# MultiSpikeHoldSchem.net
KiCad netlist of a schematic drawn in Altium Designer
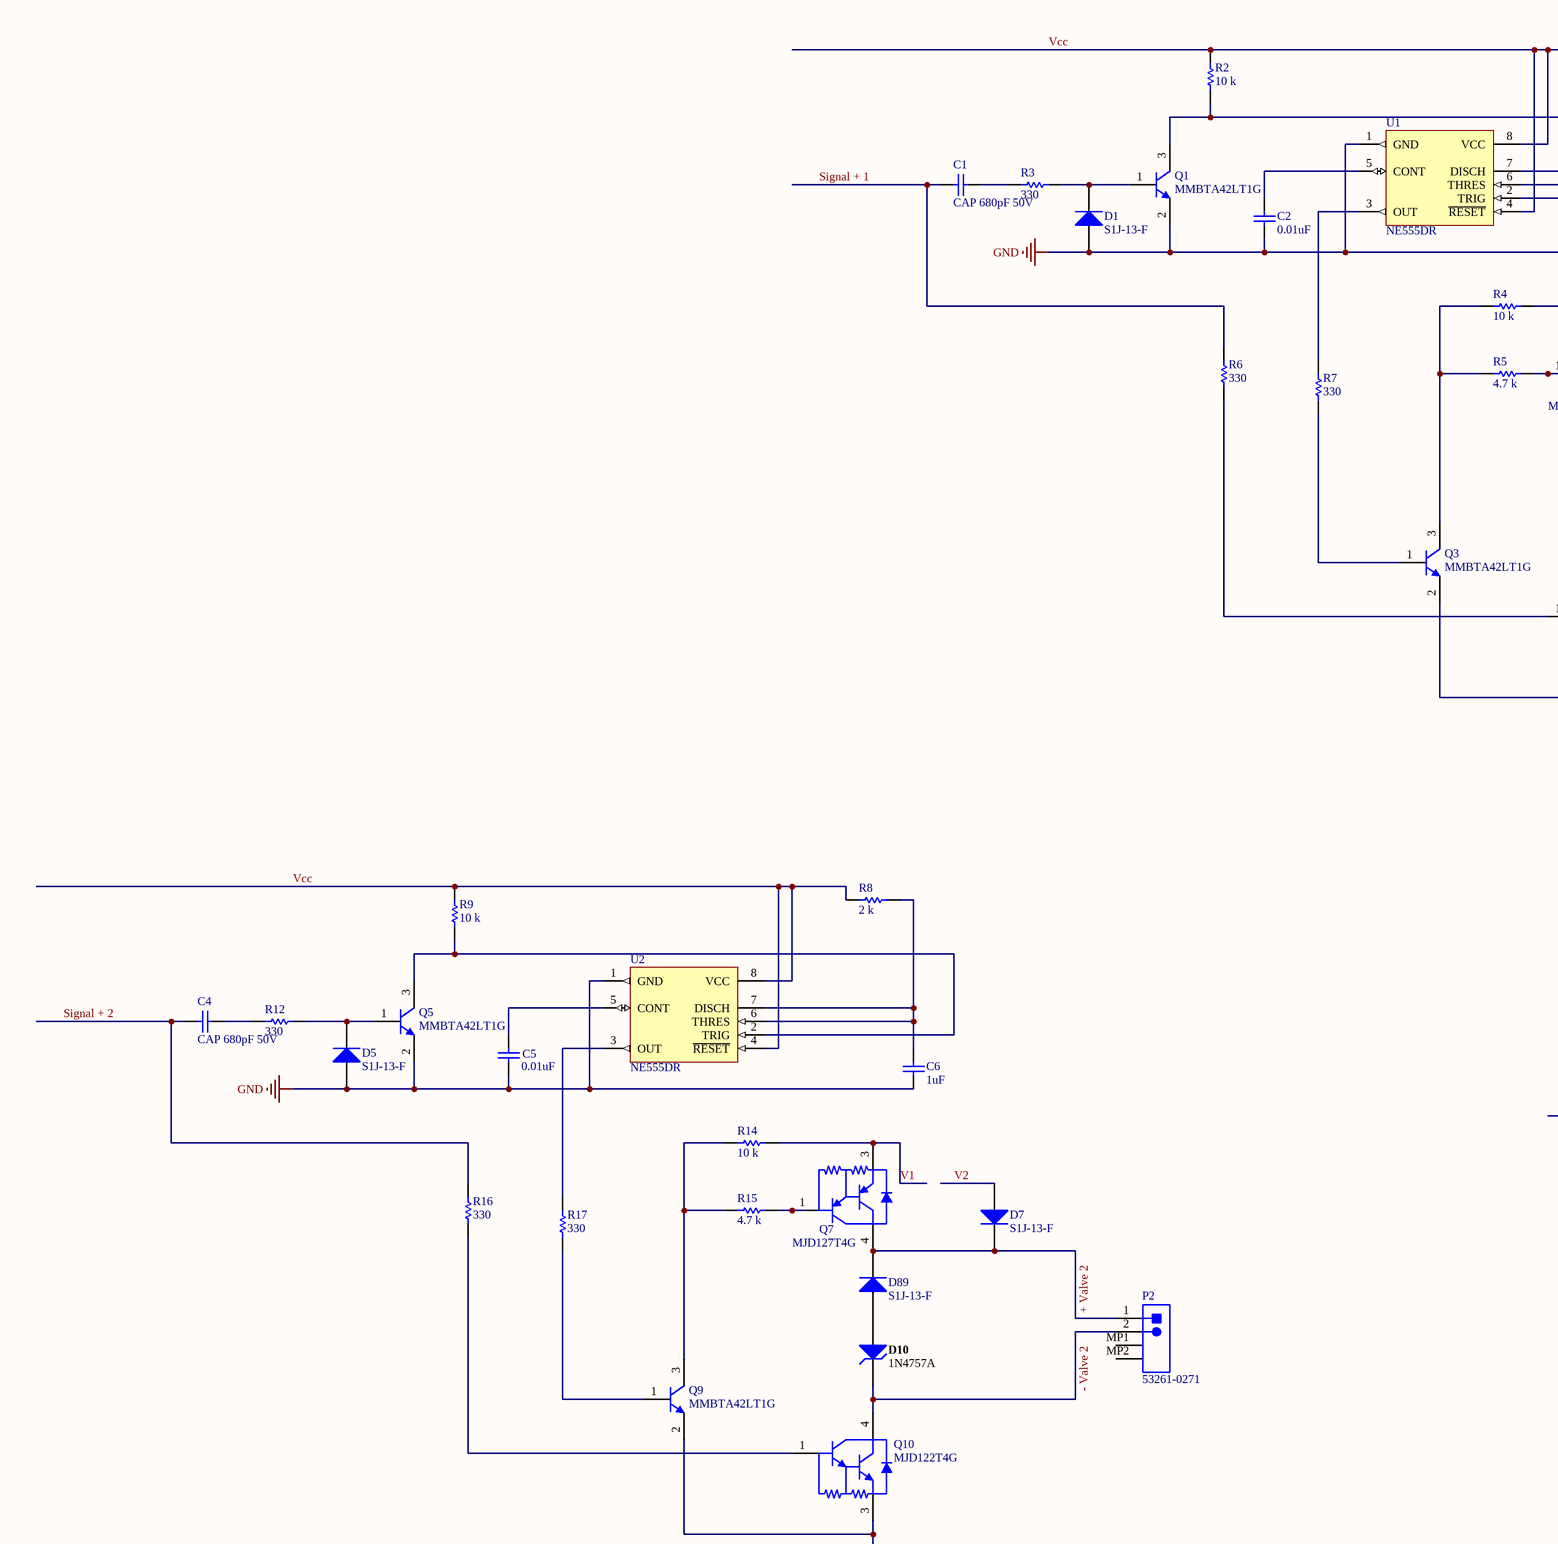
[diagram p0: MultiSpikeHoldSchem.SchDoc, top left]
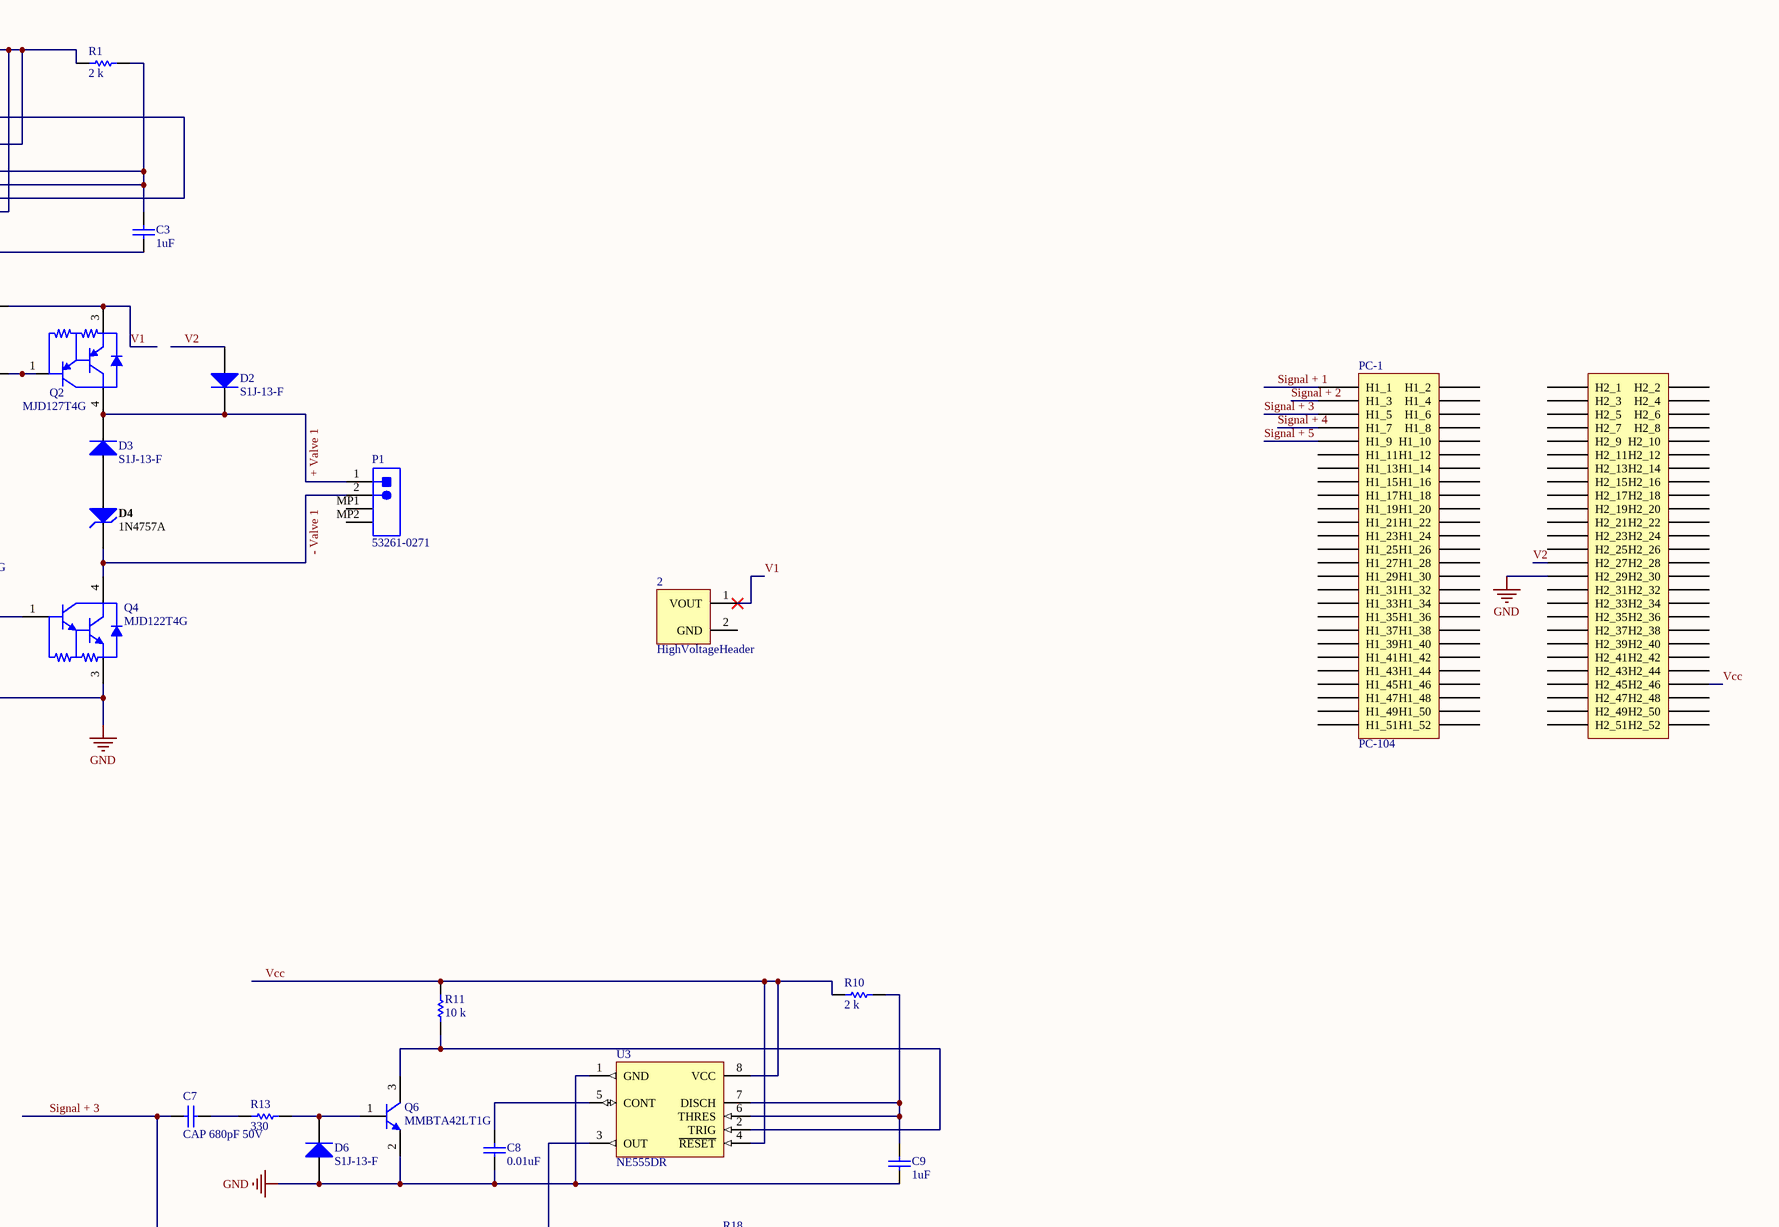
[diagram p1: MultiSpikeHoldSchem.SchDoc, top right]
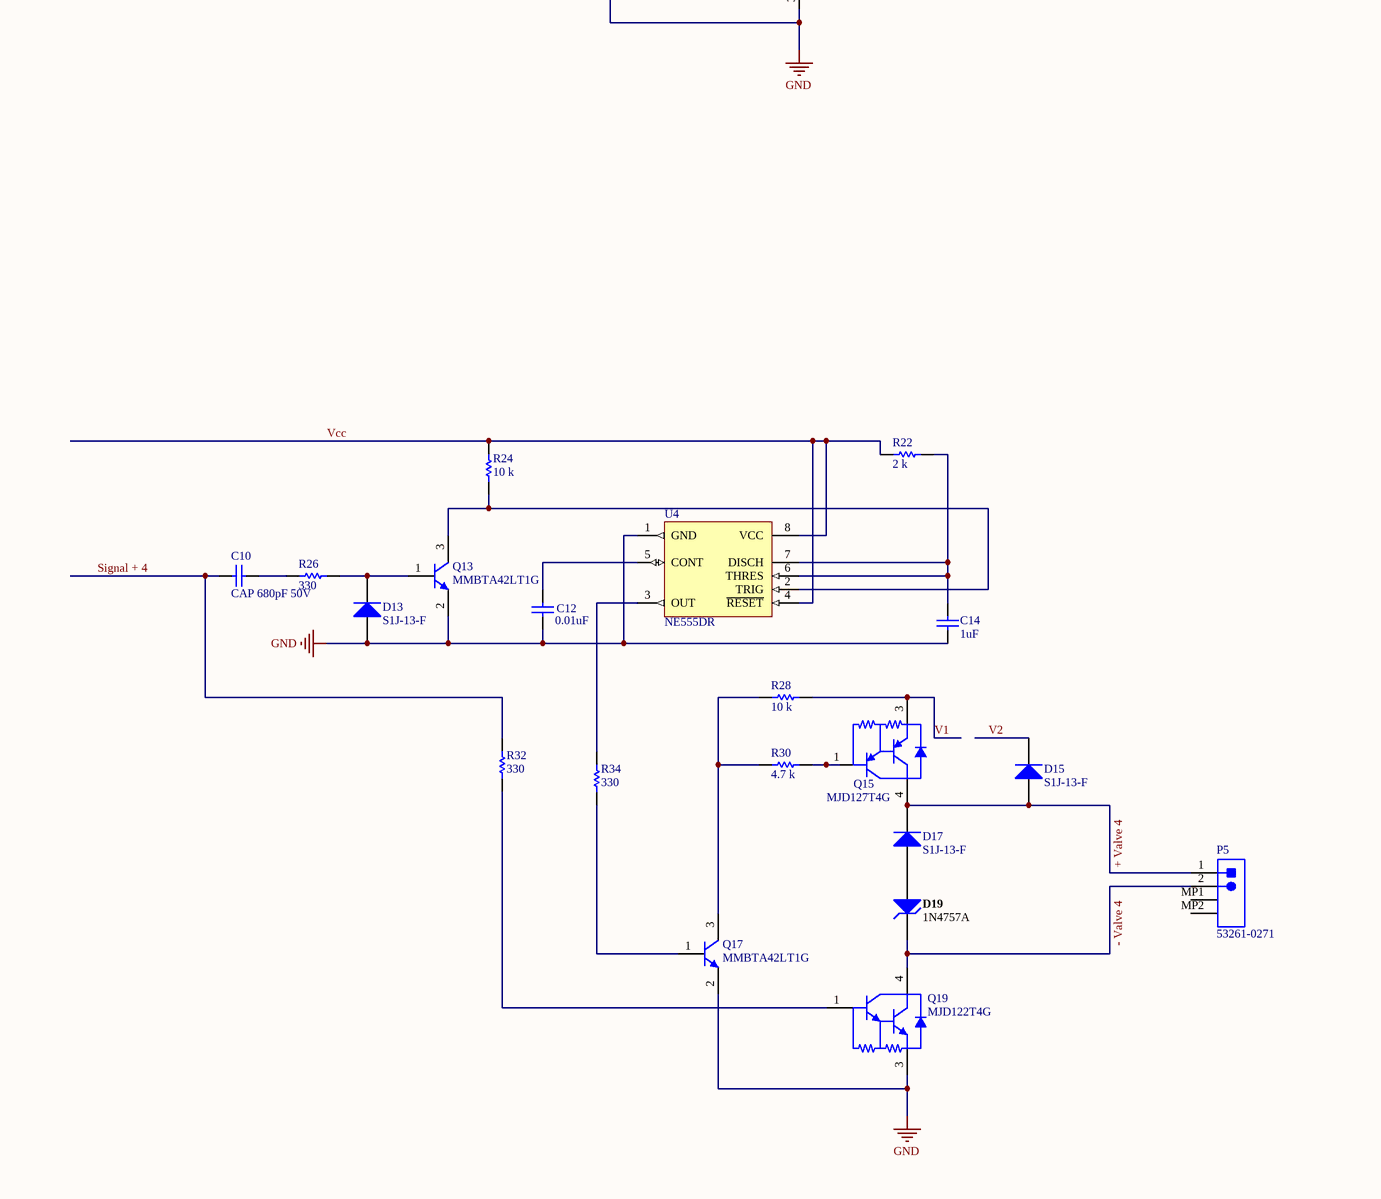
[diagram p2: MultiSpikeHoldSchem.SchDoc, bottom left]
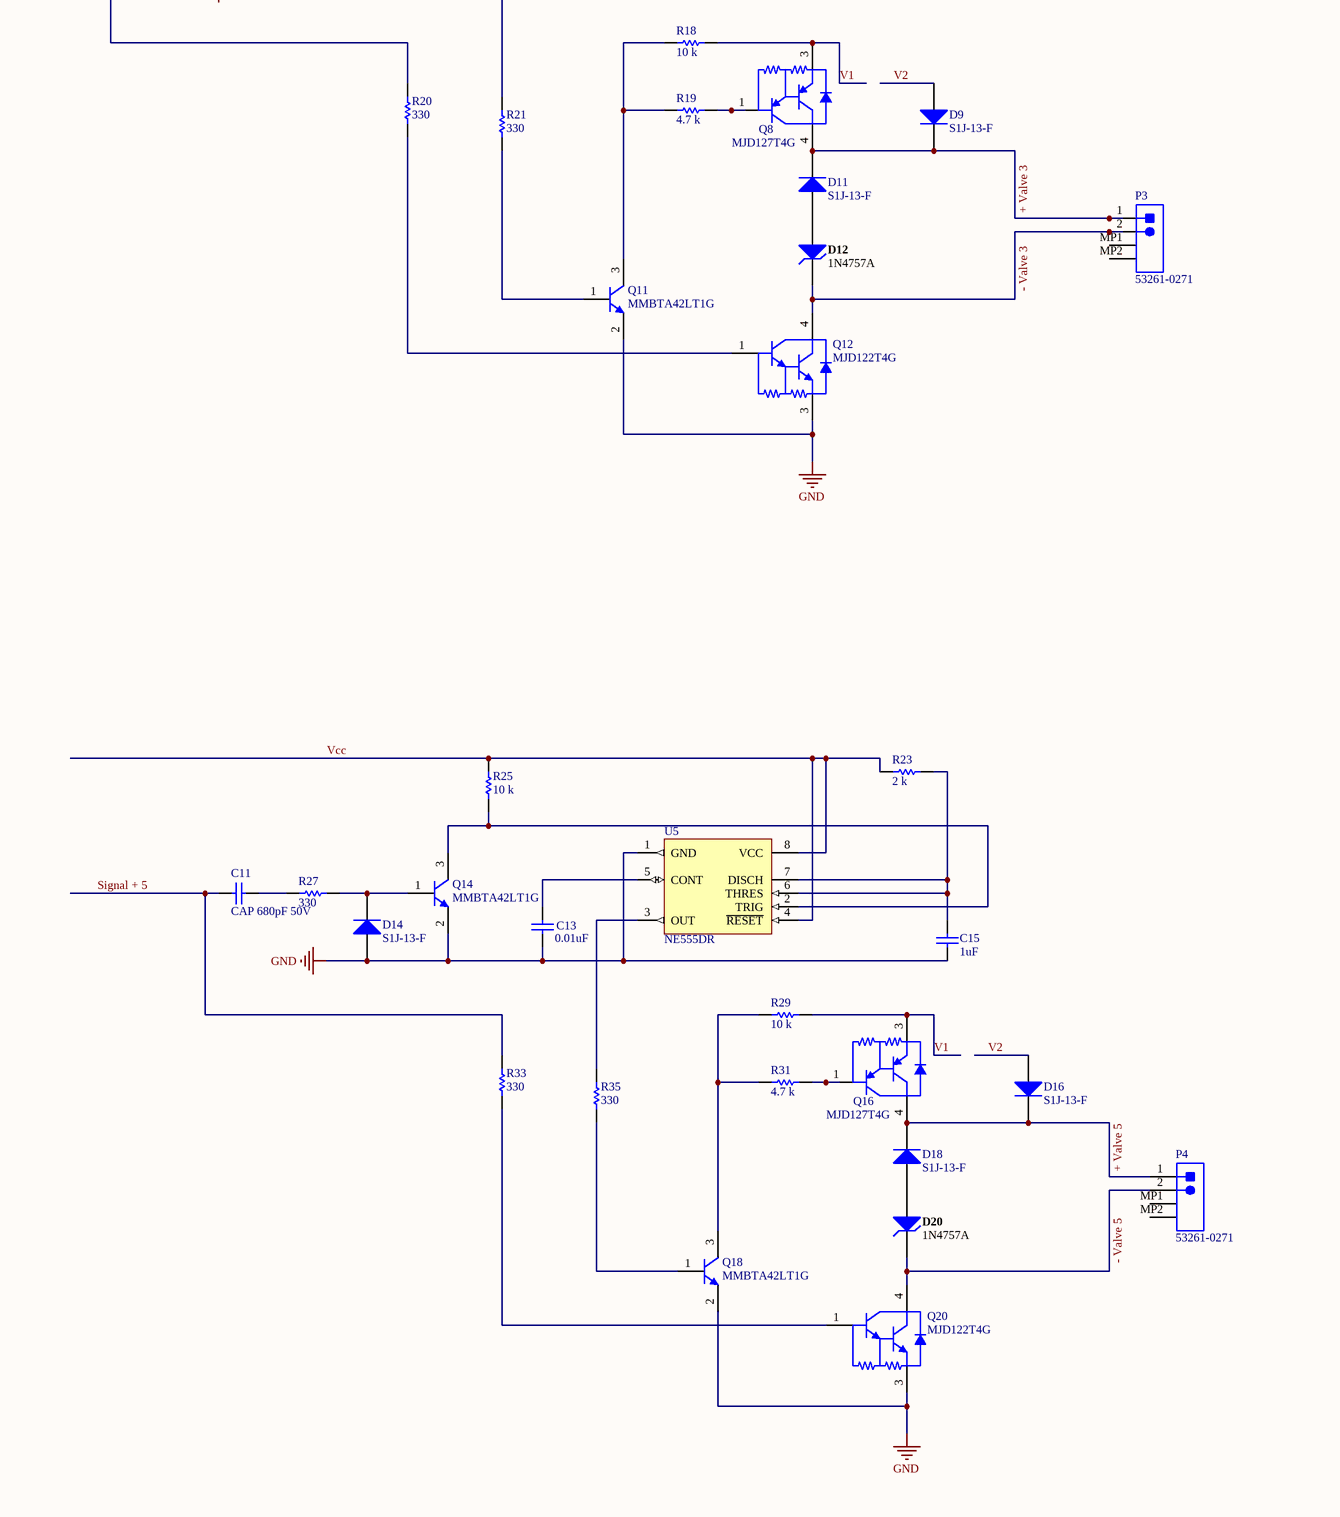
[diagram p3: MultiSpikeHoldSchem.SchDoc, bottom right]

(export (version "E")
  (design (tool "Eeschema 10.0.6"))
  (components
    (comp (ref "2")
      (value "HighVoltageHeader")
      (footprint "Header")
      (libsource (lib "AdapterBoard") (part "HighVoltageHeader"))
    )
    (comp (ref "C1")
      (value "CAP 680pF 50V")
      (footprint "CAPC1005X55X25ML05T10")
      (description "Chip Capacitor, 680 pF, +/- 10%, 50 V, -55 to 125 degC, 0402 (1005 Metric), RoHS, Tape and Reel")
      (fields (field (name "TOLERANCE") "10%") (field (name "MANUFACTURER") "Basic Passives"))
      (libsource (lib "Altium Content Vault") (part "CAP-NP-2"))
    )
    (comp (ref "C2")
      (value "0.01uF")
      (footprint "CAPC2013X70X45ML10T25")
      (description "Chip Capacitor, 10 nF, +/- 10%, 50 V, -55 to 125 degC, 0805 (2012 Metric), RoHS, Tape and Reel")
      (fields (field (name "TOLERANCE") "10%") (field (name "MANUFACTURER") "Murata"))
      (libsource (lib "Altium Content Vault") (part "CAP-NP-2"))
    )
    (comp (ref "C3")
      (value "1uF")
      (footprint "CAPC1206(3216)110_L")
      (description "CAP 1uF 50V ±10% 1206 (3216 Metric) Thickness 1.1mm SMD")
      (fields (field (name "TOLERANCE") "Â±10%"))
      (libsource (lib "Altium Content Vault") (part "CAP"))
    )
    (comp (ref "C4")
      (value "CAP 680pF 50V")
      (footprint "CAPC1005X55X25ML05T10")
      (description "Chip Capacitor, 680 pF, +/- 10%, 50 V, -55 to 125 degC, 0402 (1005 Metric), RoHS, Tape and Reel")
      (fields (field (name "TOLERANCE") "10%") (field (name "MANUFACTURER") "Basic Passives"))
      (libsource (lib "Altium Content Vault") (part "CAP-NP-2"))
    )
    (comp (ref "C5")
      (value "0.01uF")
      (footprint "CAPC2013X70X45ML10T25")
      (description "Chip Capacitor, 10 nF, +/- 10%, 50 V, -55 to 125 degC, 0805 (2012 Metric), RoHS, Tape and Reel")
      (fields (field (name "TOLERANCE") "10%") (field (name "MANUFACTURER") "Murata"))
      (libsource (lib "Altium Content Vault") (part "CAP-NP-2"))
    )
    (comp (ref "C6")
      (value "1uF")
      (footprint "CAPC1206(3216)110_L")
      (description "CAP 1uF 50V ±10% 1206 (3216 Metric) Thickness 1.1mm SMD")
      (fields (field (name "TOLERANCE") "Â±10%"))
      (libsource (lib "Altium Content Vault") (part "CAP"))
    )
    (comp (ref "C7")
      (value "CAP 680pF 50V")
      (footprint "CAPC1005X55X25ML05T10")
      (description "Chip Capacitor, 680 pF, +/- 10%, 50 V, -55 to 125 degC, 0402 (1005 Metric), RoHS, Tape and Reel")
      (fields (field (name "TOLERANCE") "10%") (field (name "MANUFACTURER") "Basic Passives"))
      (libsource (lib "Altium Content Vault") (part "CAP-NP-2"))
    )
    (comp (ref "C8")
      (value "0.01uF")
      (footprint "CAPC2013X70X45ML10T25")
      (description "Chip Capacitor, 10 nF, +/- 10%, 50 V, -55 to 125 degC, 0805 (2012 Metric), RoHS, Tape and Reel")
      (fields (field (name "TOLERANCE") "10%") (field (name "MANUFACTURER") "Murata"))
      (libsource (lib "Altium Content Vault") (part "CAP-NP-2"))
    )
    (comp (ref "C9")
      (value "1uF")
      (footprint "CAPC1206(3216)110_L")
      (description "CAP 1uF 50V ±10% 1206 (3216 Metric) Thickness 1.1mm SMD")
      (fields (field (name "TOLERANCE") "Â±10%"))
      (libsource (lib "Altium Content Vault") (part "CAP"))
    )
    (comp (ref "C10")
      (value "CAP 680pF 50V")
      (footprint "CAPC1005X55X25ML05T10")
      (description "Chip Capacitor, 680 pF, +/- 10%, 50 V, -55 to 125 degC, 0402 (1005 Metric), RoHS, Tape and Reel")
      (fields (field (name "TOLERANCE") "10%") (field (name "MANUFACTURER") "Basic Passives"))
      (libsource (lib "Altium Content Vault") (part "CAP-NP-2"))
    )
    (comp (ref "C11")
      (value "CAP 680pF 50V")
      (footprint "CAPC1005X55X25ML05T10")
      (description "Chip Capacitor, 680 pF, +/- 10%, 50 V, -55 to 125 degC, 0402 (1005 Metric), RoHS, Tape and Reel")
      (fields (field (name "TOLERANCE") "10%") (field (name "MANUFACTURER") "Basic Passives"))
      (libsource (lib "Altium Content Vault") (part "CAP-NP-2"))
    )
    (comp (ref "C12")
      (value "0.01uF")
      (footprint "CAPC2013X70X45ML10T25")
      (description "Chip Capacitor, 10 nF, +/- 10%, 50 V, -55 to 125 degC, 0805 (2012 Metric), RoHS, Tape and Reel")
      (fields (field (name "TOLERANCE") "10%") (field (name "MANUFACTURER") "Murata"))
      (libsource (lib "Altium Content Vault") (part "CAP-NP-2"))
    )
    (comp (ref "C13")
      (value "0.01uF")
      (footprint "CAPC2013X70X45ML10T25")
      (description "Chip Capacitor, 10 nF, +/- 10%, 50 V, -55 to 125 degC, 0805 (2012 Metric), RoHS, Tape and Reel")
      (fields (field (name "TOLERANCE") "10%") (field (name "MANUFACTURER") "Murata"))
      (libsource (lib "Altium Content Vault") (part "CAP-NP-2"))
    )
    (comp (ref "C14")
      (value "1uF")
      (footprint "CAPC1206(3216)110_L")
      (description "CAP 1uF 50V ±10% 1206 (3216 Metric) Thickness 1.1mm SMD")
      (fields (field (name "TOLERANCE") "Â±10%"))
      (libsource (lib "Altium Content Vault") (part "CAP"))
    )
    (comp (ref "C15")
      (value "1uF")
      (footprint "CAPC1206(3216)110_L")
      (description "CAP 1uF 50V ±10% 1206 (3216 Metric) Thickness 1.1mm SMD")
      (fields (field (name "TOLERANCE") "Â±10%"))
      (libsource (lib "Altium Content Vault") (part "CAP"))
    )
    (comp (ref "D1")
      (value "S1J-13-F")
      (footprint "DIOD-S1M-13-F-SMA-2_V")
      (fields (field (name "MANUFACTURER") "Diodes Inc") (field (name "PARTNUMBER") "S1M-13-F"))
      (libsource (lib "Altium Content Vault") (part "DIOD-D-A1K2-2"))
    )
    (comp (ref "D2")
      (value "S1J-13-F")
      (footprint "DIOD-S1M-13-F-SMA-2_V")
      (fields (field (name "MANUFACTURER") "Diodes Inc") (field (name "PARTNUMBER") "S1M-13-F"))
      (libsource (lib "Altium Content Vault") (part "DIOD-D-A1K2-2"))
    )
    (comp (ref "D3")
      (value "S1J-13-F")
      (footprint "DIOD-S1M-13-F-SMA-2_V")
      (fields (field (name "MANUFACTURER") "Diodes Inc") (field (name "PARTNUMBER") "S1M-13-F"))
      (libsource (lib "Altium Content Vault") (part "DIOD-D-A1K2-2"))
    )
    (comp (ref "D4")
      (value "1N4757A")
      (footprint "FAIR-DO-41-2_V")
      (description "Zener Diode, 51V, 1W, 5%, -65 to 200 degC, 2-Pin DO-41, Body 2.72 x 5.2 mm, RoHS")
      (fields (field (name "MANUFACTURER") "Fairchild Semiconductor") (field (name "TOLERANCE") "5%"))
      (libsource (lib "Altium Content Vault") (part "FAIR-DZEN-A1K2-2"))
    )
    (comp (ref "D5")
      (value "S1J-13-F")
      (footprint "DIOD-S1M-13-F-SMA-2_V")
      (fields (field (name "MANUFACTURER") "Diodes Inc") (field (name "PARTNUMBER") "S1M-13-F"))
      (libsource (lib "Altium Content Vault") (part "DIOD-D-A1K2-2"))
    )
    (comp (ref "D6")
      (value "S1J-13-F")
      (footprint "DIOD-S1M-13-F-SMA-2_V")
      (fields (field (name "MANUFACTURER") "Diodes Inc") (field (name "PARTNUMBER") "S1M-13-F"))
      (libsource (lib "Altium Content Vault") (part "DIOD-D-A1K2-2"))
    )
    (comp (ref "D7")
      (value "S1J-13-F")
      (footprint "DIOD-S1M-13-F-SMA-2_V")
      (fields (field (name "MANUFACTURER") "Diodes Inc") (field (name "PARTNUMBER") "S1M-13-F"))
      (libsource (lib "Altium Content Vault") (part "DIOD-D-A1K2-2"))
    )
    (comp (ref "D9")
      (value "S1J-13-F")
      (footprint "DIOD-S1M-13-F-SMA-2_V")
      (fields (field (name "MANUFACTURER") "Diodes Inc") (field (name "PARTNUMBER") "S1M-13-F"))
      (libsource (lib "Altium Content Vault") (part "DIOD-D-A1K2-2"))
    )
    (comp (ref "D10")
      (value "1N4757A")
      (footprint "FAIR-DO-41-2_V")
      (description "Zener Diode, 51V, 1W, 5%, -65 to 200 degC, 2-Pin DO-41, Body 2.72 x 5.2 mm, RoHS")
      (fields (field (name "MANUFACTURER") "Fairchild Semiconductor") (field (name "TOLERANCE") "5%"))
      (libsource (lib "Altium Content Vault") (part "FAIR-DZEN-A1K2-2"))
    )
    (comp (ref "D11")
      (value "S1J-13-F")
      (footprint "DIOD-S1M-13-F-SMA-2_V")
      (fields (field (name "MANUFACTURER") "Diodes Inc") (field (name "PARTNUMBER") "S1M-13-F"))
      (libsource (lib "Altium Content Vault") (part "DIOD-D-A1K2-2"))
    )
    (comp (ref "D12")
      (value "1N4757A")
      (footprint "FAIR-DO-41-2_V")
      (description "Zener Diode, 51V, 1W, 5%, -65 to 200 degC, 2-Pin DO-41, Body 2.72 x 5.2 mm, RoHS")
      (fields (field (name "MANUFACTURER") "Fairchild Semiconductor") (field (name "TOLERANCE") "5%"))
      (libsource (lib "Altium Content Vault") (part "FAIR-DZEN-A1K2-2"))
    )
    (comp (ref "D13")
      (value "S1J-13-F")
      (footprint "DIOD-S1M-13-F-SMA-2_V")
      (fields (field (name "MANUFACTURER") "Diodes Inc") (field (name "PARTNUMBER") "S1M-13-F"))
      (libsource (lib "Altium Content Vault") (part "DIOD-D-A1K2-2"))
    )
    (comp (ref "D14")
      (value "S1J-13-F")
      (footprint "DIOD-S1M-13-F-SMA-2_V")
      (fields (field (name "MANUFACTURER") "Diodes Inc") (field (name "PARTNUMBER") "S1M-13-F"))
      (libsource (lib "Altium Content Vault") (part "DIOD-D-A1K2-2"))
    )
    (comp (ref "D15")
      (value "S1J-13-F")
      (footprint "DIOD-S1M-13-F-SMA-2_V")
      (fields (field (name "MANUFACTURER") "Diodes Inc") (field (name "PARTNUMBER") "S1M-13-F"))
      (libsource (lib "Altium Content Vault") (part "DIOD-D-A1K2-2"))
    )
    (comp (ref "D16")
      (value "S1J-13-F")
      (footprint "DIOD-S1M-13-F-SMA-2_V")
      (fields (field (name "MANUFACTURER") "Diodes Inc") (field (name "PARTNUMBER") "S1M-13-F"))
      (libsource (lib "Altium Content Vault") (part "DIOD-D-A1K2-2"))
    )
    (comp (ref "D17")
      (value "S1J-13-F")
      (footprint "DIOD-S1M-13-F-SMA-2_V")
      (fields (field (name "MANUFACTURER") "Diodes Inc") (field (name "PARTNUMBER") "S1M-13-F"))
      (libsource (lib "Altium Content Vault") (part "DIOD-D-A1K2-2"))
    )
    (comp (ref "D18")
      (value "S1J-13-F")
      (footprint "DIOD-S1M-13-F-SMA-2_V")
      (fields (field (name "MANUFACTURER") "Diodes Inc") (field (name "PARTNUMBER") "S1M-13-F"))
      (libsource (lib "Altium Content Vault") (part "DIOD-D-A1K2-2"))
    )
    (comp (ref "D19")
      (value "1N4757A")
      (footprint "FAIR-DO-41-2_V")
      (description "Zener Diode, 51V, 1W, 5%, -65 to 200 degC, 2-Pin DO-41, Body 2.72 x 5.2 mm, RoHS")
      (fields (field (name "MANUFACTURER") "Fairchild Semiconductor") (field (name "TOLERANCE") "5%"))
      (libsource (lib "Altium Content Vault") (part "FAIR-DZEN-A1K2-2"))
    )
    (comp (ref "D20")
      (value "1N4757A")
      (footprint "FAIR-DO-41-2_V")
      (description "Zener Diode, 51V, 1W, 5%, -65 to 200 degC, 2-Pin DO-41, Body 2.72 x 5.2 mm, RoHS")
      (fields (field (name "MANUFACTURER") "Fairchild Semiconductor") (field (name "TOLERANCE") "5%"))
      (libsource (lib "Altium Content Vault") (part "FAIR-DZEN-A1K2-2"))
    )
    (comp (ref "D89")
      (value "S1J-13-F")
      (footprint "DIOD-S1M-13-F-SMA-2_V")
      (fields (field (name "MANUFACTURER") "Diodes Inc") (field (name "PARTNUMBER") "S1M-13-F"))
      (libsource (lib "Altium Content Vault") (part "DIOD-D-A1K2-2"))
    )
    (comp (ref "P1")
      (value "53261-0271")
      (footprint "MOLX-53261-0271_V")
      (description "PicoBlade(TM) Header, Right Angle, -40 to 85 degC, 2-Pin SMD, RoHS, Tape and Reel")
      (fields (field (name "MANUFACTURER") "Molex"))
      (libsource (lib "Altium Content Vault") (part "CN-1P-2M-R2"))
    )
    (comp (ref "P2")
      (value "53261-0271")
      (footprint "MOLX-53261-0271_V")
      (description "PicoBlade(TM) Header, Right Angle, -40 to 85 degC, 2-Pin SMD, RoHS, Tape and Reel")
      (fields (field (name "MANUFACTURER") "Molex"))
      (libsource (lib "Altium Content Vault") (part "CN-1P-2M-R2"))
    )
    (comp (ref "P3")
      (value "53261-0271")
      (footprint "MOLX-53261-0271_V")
      (description "PicoBlade(TM) Header, Right Angle, -40 to 85 degC, 2-Pin SMD, RoHS, Tape and Reel")
      (fields (field (name "MANUFACTURER") "Molex"))
      (libsource (lib "Altium Content Vault") (part "CN-1P-2M-R2"))
    )
    (comp (ref "P4")
      (value "53261-0271")
      (footprint "MOLX-53261-0271_V")
      (description "PicoBlade(TM) Header, Right Angle, -40 to 85 degC, 2-Pin SMD, RoHS, Tape and Reel")
      (fields (field (name "MANUFACTURER") "Molex"))
      (libsource (lib "Altium Content Vault") (part "CN-1P-2M-R2"))
    )
    (comp (ref "P5")
      (value "53261-0271")
      (footprint "MOLX-53261-0271_V")
      (description "PicoBlade(TM) Header, Right Angle, -40 to 85 degC, 2-Pin SMD, RoHS, Tape and Reel")
      (fields (field (name "MANUFACTURER") "Molex"))
      (libsource (lib "Altium Content Vault") (part "CN-1P-2M-R2"))
    )
    (comp (ref "PC-1")
      (value "PC-104")
      (footprint "PC-104FOOTPRINT")
      (libsource (lib "UmbilicalBoardV3") (part "PC-104"))
    )
    (comp (ref "Q1")
      (value "MMBTA42LT1G")
      (footprint "ONSC-SOT-23-3-318-08_V")
      (description "High Voltage Transistor, NPN Silicon, 3-Pin SOT-23, Pb-Free, Tape and Reel")
      (fields (field (name "MANUFACTURER") "On Semiconductor"))
      (libsource (lib "Altium Content Vault") (part "CMP-1048-00662-1"))
    )
    (comp (ref "Q2")
      (value "MJD127T4G")
      (footprint "ONSC-DPAK-3-369C-01_V")
      (description "Complementary Darlington Power Transistor, 3-Pin DPAK, Pb-Free, Tape and Reel")
      (fields (field (name "MANUFACTURER") "On Semiconductor"))
      (libsource (lib "Altium Content Vault") (part "CMP-1047-00009-1"))
    )
    (comp (ref "Q3")
      (value "MMBTA42LT1G")
      (footprint "ONSC-SOT-23-3-318-08_V")
      (description "High Voltage Transistor, NPN Silicon, 3-Pin SOT-23, Pb-Free, Tape and Reel")
      (fields (field (name "MANUFACTURER") "On Semiconductor"))
      (libsource (lib "Altium Content Vault") (part "CMP-1048-00662-1"))
    )
    (comp (ref "Q4")
      (value "MJD122T4G")
      (footprint "ONSC-DPAK-3-369C-01_V")
      (description "Complementary Darlington Power Transistor, 3-Pin DPAK, Pb-Free, Tape and Reel")
      (fields (field (name "MANUFACTURER") "On Semiconductor"))
      (libsource (lib "Altium Content Vault") (part "CMP-1047-00007-1"))
    )
    (comp (ref "Q5")
      (value "MMBTA42LT1G")
      (footprint "ONSC-SOT-23-3-318-08_V")
      (description "High Voltage Transistor, NPN Silicon, 3-Pin SOT-23, Pb-Free, Tape and Reel")
      (fields (field (name "MANUFACTURER") "On Semiconductor"))
      (libsource (lib "Altium Content Vault") (part "CMP-1048-00662-1"))
    )
    (comp (ref "Q6")
      (value "MMBTA42LT1G")
      (footprint "ONSC-SOT-23-3-318-08_V")
      (description "High Voltage Transistor, NPN Silicon, 3-Pin SOT-23, Pb-Free, Tape and Reel")
      (fields (field (name "MANUFACTURER") "On Semiconductor"))
      (libsource (lib "Altium Content Vault") (part "CMP-1048-00662-1"))
    )
    (comp (ref "Q7")
      (value "MJD127T4G")
      (footprint "ONSC-DPAK-3-369C-01_V")
      (description "Complementary Darlington Power Transistor, 3-Pin DPAK, Pb-Free, Tape and Reel")
      (fields (field (name "MANUFACTURER") "On Semiconductor"))
      (libsource (lib "Altium Content Vault") (part "CMP-1047-00009-1"))
    )
    (comp (ref "Q8")
      (value "MJD127T4G")
      (footprint "ONSC-DPAK-3-369C-01_V")
      (description "Complementary Darlington Power Transistor, 3-Pin DPAK, Pb-Free, Tape and Reel")
      (fields (field (name "MANUFACTURER") "On Semiconductor"))
      (libsource (lib "Altium Content Vault") (part "CMP-1047-00009-1"))
    )
    (comp (ref "Q9")
      (value "MMBTA42LT1G")
      (footprint "ONSC-SOT-23-3-318-08_V")
      (description "High Voltage Transistor, NPN Silicon, 3-Pin SOT-23, Pb-Free, Tape and Reel")
      (fields (field (name "MANUFACTURER") "On Semiconductor"))
      (libsource (lib "Altium Content Vault") (part "CMP-1048-00662-1"))
    )
    (comp (ref "Q10")
      (value "MJD122T4G")
      (footprint "ONSC-DPAK-3-369C-01_V")
      (description "Complementary Darlington Power Transistor, 3-Pin DPAK, Pb-Free, Tape and Reel")
      (fields (field (name "MANUFACTURER") "On Semiconductor"))
      (libsource (lib "Altium Content Vault") (part "CMP-1047-00007-1"))
    )
    (comp (ref "Q11")
      (value "MMBTA42LT1G")
      (footprint "ONSC-SOT-23-3-318-08_V")
      (description "High Voltage Transistor, NPN Silicon, 3-Pin SOT-23, Pb-Free, Tape and Reel")
      (fields (field (name "MANUFACTURER") "On Semiconductor"))
      (libsource (lib "Altium Content Vault") (part "CMP-1048-00662-1"))
    )
    (comp (ref "Q12")
      (value "MJD122T4G")
      (footprint "ONSC-DPAK-3-369C-01_V")
      (description "Complementary Darlington Power Transistor, 3-Pin DPAK, Pb-Free, Tape and Reel")
      (fields (field (name "MANUFACTURER") "On Semiconductor"))
      (libsource (lib "Altium Content Vault") (part "CMP-1047-00007-1"))
    )
    (comp (ref "Q13")
      (value "MMBTA42LT1G")
      (footprint "ONSC-SOT-23-3-318-08_V")
      (description "High Voltage Transistor, NPN Silicon, 3-Pin SOT-23, Pb-Free, Tape and Reel")
      (fields (field (name "MANUFACTURER") "On Semiconductor"))
      (libsource (lib "Altium Content Vault") (part "CMP-1048-00662-1"))
    )
    (comp (ref "Q14")
      (value "MMBTA42LT1G")
      (footprint "ONSC-SOT-23-3-318-08_V")
      (description "High Voltage Transistor, NPN Silicon, 3-Pin SOT-23, Pb-Free, Tape and Reel")
      (fields (field (name "MANUFACTURER") "On Semiconductor"))
      (libsource (lib "Altium Content Vault") (part "CMP-1048-00662-1"))
    )
    (comp (ref "Q15")
      (value "MJD127T4G")
      (footprint "ONSC-DPAK-3-369C-01_V")
      (description "Complementary Darlington Power Transistor, 3-Pin DPAK, Pb-Free, Tape and Reel")
      (fields (field (name "MANUFACTURER") "On Semiconductor"))
      (libsource (lib "Altium Content Vault") (part "CMP-1047-00009-1"))
    )
    (comp (ref "Q16")
      (value "MJD127T4G")
      (footprint "ONSC-DPAK-3-369C-01_V")
      (description "Complementary Darlington Power Transistor, 3-Pin DPAK, Pb-Free, Tape and Reel")
      (fields (field (name "MANUFACTURER") "On Semiconductor"))
      (libsource (lib "Altium Content Vault") (part "CMP-1047-00009-1"))
    )
    (comp (ref "Q17")
      (value "MMBTA42LT1G")
      (footprint "ONSC-SOT-23-3-318-08_V")
      (description "High Voltage Transistor, NPN Silicon, 3-Pin SOT-23, Pb-Free, Tape and Reel")
      (fields (field (name "MANUFACTURER") "On Semiconductor"))
      (libsource (lib "Altium Content Vault") (part "CMP-1048-00662-1"))
    )
    (comp (ref "Q18")
      (value "MMBTA42LT1G")
      (footprint "ONSC-SOT-23-3-318-08_V")
      (description "High Voltage Transistor, NPN Silicon, 3-Pin SOT-23, Pb-Free, Tape and Reel")
      (fields (field (name "MANUFACTURER") "On Semiconductor"))
      (libsource (lib "Altium Content Vault") (part "CMP-1048-00662-1"))
    )
    (comp (ref "Q19")
      (value "MJD122T4G")
      (footprint "ONSC-DPAK-3-369C-01_V")
      (description "Complementary Darlington Power Transistor, 3-Pin DPAK, Pb-Free, Tape and Reel")
      (fields (field (name "MANUFACTURER") "On Semiconductor"))
      (libsource (lib "Altium Content Vault") (part "CMP-1047-00007-1"))
    )
    (comp (ref "Q20")
      (value "MJD122T4G")
      (footprint "ONSC-DPAK-3-369C-01_V")
      (description "Complementary Darlington Power Transistor, 3-Pin DPAK, Pb-Free, Tape and Reel")
      (fields (field (name "MANUFACTURER") "On Semiconductor"))
      (libsource (lib "Altium Content Vault") (part "CMP-1047-00007-1"))
    )
    (comp (ref "R1")
      (value "2 k")
      (footprint "RESC2013X60X35ML10T20")
      (fields (field (name "MANUFACTURER") "Yageo") (field (name "PART NUMBER") "RC0805JR-072KL"))
      (libsource (lib "Altium Content Vault") (part "RES"))
    )
    (comp (ref "R2")
      (value "10 k")
      (footprint "RESC3116X65X40ML10T20")
      (description "Chip Resistor, 10 KOhm, +/- 1%, 0.25 W, -55 to 155 degC, 1206 (3216 Metric), RoHS, Tape and Reel")
      (fields (field (name "TOLERANCE") "1%") (field (name "MANUFACTURER") "Yageo"))
      (libsource (lib "Altium Content Vault") (part "RES-2"))
    )
    (comp (ref "R3")
      (value "330")
      (footprint "RESC3116X65X40LL10T20")
      (description "Chip Resistor, 330 Ohm, +/- 1%, 250 mW, -55 to 155 degC, 1206 (3216 Metric), RoHS, Tape and Reel")
      (fields (field (name "MANUFACTURER") "Yageo") (field (name "TOLERANCE") "1%"))
      (libsource (lib "Altium Content Vault") (part "RES-2"))
    )
    (comp (ref "R4")
      (value "10 k")
      (footprint "RESC3116X65X40ML10T20")
      (description "Chip Resistor, 10 KOhm, +/- 1%, 0.25 W, -55 to 155 degC, 1206 (3216 Metric), RoHS, Tape and Reel")
      (fields (field (name "TOLERANCE") "1%") (field (name "MANUFACTURER") "Yageo"))
      (libsource (lib "Altium Content Vault") (part "RES-2"))
    )
    (comp (ref "R5")
      (value "4.7 k")
      (footprint "YAGO-RC0805_M")
      (fields
        (field (name "TOLERANCE") "+/- 1%")
        (field (name "PARTNUMBER") "RC0805FR-074K7L")
        (field (name "POWER") "0.125 W")
      )
      (libsource (lib "Altium Content Vault") (part "YAGO-RES-2"))
    )
    (comp (ref "R6")
      (value "330")
      (footprint "RESC3116X65X40LL10T20")
      (description "Chip Resistor, 330 Ohm, +/- 1%, 250 mW, -55 to 155 degC, 1206 (3216 Metric), RoHS, Tape and Reel")
      (fields (field (name "MANUFACTURER") "Yageo") (field (name "TOLERANCE") "1%"))
      (libsource (lib "Altium Content Vault") (part "RES-2"))
    )
    (comp (ref "R7")
      (value "330")
      (footprint "RESC3116X65X40LL10T20")
      (description "Chip Resistor, 330 Ohm, +/- 1%, 250 mW, -55 to 155 degC, 1206 (3216 Metric), RoHS, Tape and Reel")
      (fields (field (name "MANUFACTURER") "Yageo") (field (name "TOLERANCE") "1%"))
      (libsource (lib "Altium Content Vault") (part "RES-2"))
    )
    (comp (ref "R8")
      (value "2 k")
      (footprint "RESC2013X60X35ML10T20")
      (fields (field (name "MANUFACTURER") "Yageo") (field (name "PART NUMBER") "RC0805JR-072KL"))
      (libsource (lib "Altium Content Vault") (part "RES"))
    )
    (comp (ref "R9")
      (value "10 k")
      (footprint "RESC3116X65X40ML10T20")
      (description "Chip Resistor, 10 KOhm, +/- 1%, 0.25 W, -55 to 155 degC, 1206 (3216 Metric), RoHS, Tape and Reel")
      (fields (field (name "TOLERANCE") "1%") (field (name "MANUFACTURER") "Yageo"))
      (libsource (lib "Altium Content Vault") (part "RES-2"))
    )
    (comp (ref "R10")
      (value "2 k")
      (footprint "RESC2013X60X35ML10T20")
      (fields (field (name "MANUFACTURER") "Yageo") (field (name "PART NUMBER") "RC0805JR-072KL"))
      (libsource (lib "Altium Content Vault") (part "RES"))
    )
    (comp (ref "R11")
      (value "10 k")
      (footprint "RESC3116X65X40ML10T20")
      (description "Chip Resistor, 10 KOhm, +/- 1%, 0.25 W, -55 to 155 degC, 1206 (3216 Metric), RoHS, Tape and Reel")
      (fields (field (name "TOLERANCE") "1%") (field (name "MANUFACTURER") "Yageo"))
      (libsource (lib "Altium Content Vault") (part "RES-2"))
    )
    (comp (ref "R12")
      (value "330")
      (footprint "RESC3116X65X40LL10T20")
      (description "Chip Resistor, 330 Ohm, +/- 1%, 250 mW, -55 to 155 degC, 1206 (3216 Metric), RoHS, Tape and Reel")
      (fields (field (name "MANUFACTURER") "Yageo") (field (name "TOLERANCE") "1%"))
      (libsource (lib "Altium Content Vault") (part "RES-2"))
    )
    (comp (ref "R13")
      (value "330")
      (footprint "RESC3116X65X40LL10T20")
      (description "Chip Resistor, 330 Ohm, +/- 1%, 250 mW, -55 to 155 degC, 1206 (3216 Metric), RoHS, Tape and Reel")
      (fields (field (name "MANUFACTURER") "Yageo") (field (name "TOLERANCE") "1%"))
      (libsource (lib "Altium Content Vault") (part "RES-2"))
    )
    (comp (ref "R14")
      (value "10 k")
      (footprint "RESC3116X65X40ML10T20")
      (description "Chip Resistor, 10 KOhm, +/- 1%, 0.25 W, -55 to 155 degC, 1206 (3216 Metric), RoHS, Tape and Reel")
      (fields (field (name "TOLERANCE") "1%") (field (name "MANUFACTURER") "Yageo"))
      (libsource (lib "Altium Content Vault") (part "RES-2"))
    )
    (comp (ref "R15")
      (value "4.7 k")
      (footprint "YAGO-RC0805_M")
      (fields
        (field (name "TOLERANCE") "+/- 1%")
        (field (name "PARTNUMBER") "RC0805FR-074K7L")
        (field (name "POWER") "0.125 W")
      )
      (libsource (lib "Altium Content Vault") (part "YAGO-RES-2"))
    )
    (comp (ref "R16")
      (value "330")
      (footprint "RESC3116X65X40LL10T20")
      (description "Chip Resistor, 330 Ohm, +/- 1%, 250 mW, -55 to 155 degC, 1206 (3216 Metric), RoHS, Tape and Reel")
      (fields (field (name "MANUFACTURER") "Yageo") (field (name "TOLERANCE") "1%"))
      (libsource (lib "Altium Content Vault") (part "RES-2"))
    )
    (comp (ref "R17")
      (value "330")
      (footprint "RESC3116X65X40LL10T20")
      (description "Chip Resistor, 330 Ohm, +/- 1%, 250 mW, -55 to 155 degC, 1206 (3216 Metric), RoHS, Tape and Reel")
      (fields (field (name "MANUFACTURER") "Yageo") (field (name "TOLERANCE") "1%"))
      (libsource (lib "Altium Content Vault") (part "RES-2"))
    )
    (comp (ref "R18")
      (value "10 k")
      (footprint "RESC3116X65X40ML10T20")
      (description "Chip Resistor, 10 KOhm, +/- 1%, 0.25 W, -55 to 155 degC, 1206 (3216 Metric), RoHS, Tape and Reel")
      (fields (field (name "TOLERANCE") "1%") (field (name "MANUFACTURER") "Yageo"))
      (libsource (lib "Altium Content Vault") (part "RES-2"))
    )
    (comp (ref "R19")
      (value "4.7 k")
      (footprint "YAGO-RC0805_M")
      (fields
        (field (name "TOLERANCE") "+/- 1%")
        (field (name "PARTNUMBER") "RC0805FR-074K7L")
        (field (name "POWER") "0.125 W")
      )
      (libsource (lib "Altium Content Vault") (part "YAGO-RES-2"))
    )
    (comp (ref "R20")
      (value "330")
      (footprint "RESC3116X65X40LL10T20")
      (description "Chip Resistor, 330 Ohm, +/- 1%, 250 mW, -55 to 155 degC, 1206 (3216 Metric), RoHS, Tape and Reel")
      (fields (field (name "MANUFACTURER") "Yageo") (field (name "TOLERANCE") "1%"))
      (libsource (lib "Altium Content Vault") (part "RES-2"))
    )
    (comp (ref "R21")
      (value "330")
      (footprint "RESC3116X65X40LL10T20")
      (description "Chip Resistor, 330 Ohm, +/- 1%, 250 mW, -55 to 155 degC, 1206 (3216 Metric), RoHS, Tape and Reel")
      (fields (field (name "MANUFACTURER") "Yageo") (field (name "TOLERANCE") "1%"))
      (libsource (lib "Altium Content Vault") (part "RES-2"))
    )
    (comp (ref "R22")
      (value "2 k")
      (footprint "RESC2013X60X35ML10T20")
      (fields (field (name "MANUFACTURER") "Yageo") (field (name "PART NUMBER") "RC0805JR-072KL"))
      (libsource (lib "Altium Content Vault") (part "RES"))
    )
    (comp (ref "R23")
      (value "2 k")
      (footprint "RESC2013X60X35ML10T20")
      (fields (field (name "MANUFACTURER") "Yageo") (field (name "PART NUMBER") "RC0805JR-072KL"))
      (libsource (lib "Altium Content Vault") (part "RES"))
    )
    (comp (ref "R24")
      (value "10 k")
      (footprint "RESC3116X65X40ML10T20")
      (description "Chip Resistor, 10 KOhm, +/- 1%, 0.25 W, -55 to 155 degC, 1206 (3216 Metric), RoHS, Tape and Reel")
      (fields (field (name "TOLERANCE") "1%") (field (name "MANUFACTURER") "Yageo"))
      (libsource (lib "Altium Content Vault") (part "RES-2"))
    )
    (comp (ref "R25")
      (value "10 k")
      (footprint "RESC3116X65X40ML10T20")
      (description "Chip Resistor, 10 KOhm, +/- 1%, 0.25 W, -55 to 155 degC, 1206 (3216 Metric), RoHS, Tape and Reel")
      (fields (field (name "TOLERANCE") "1%") (field (name "MANUFACTURER") "Yageo"))
      (libsource (lib "Altium Content Vault") (part "RES-2"))
    )
    (comp (ref "R26")
      (value "330")
      (footprint "RESC3116X65X40LL10T20")
      (description "Chip Resistor, 330 Ohm, +/- 1%, 250 mW, -55 to 155 degC, 1206 (3216 Metric), RoHS, Tape and Reel")
      (fields (field (name "MANUFACTURER") "Yageo") (field (name "TOLERANCE") "1%"))
      (libsource (lib "Altium Content Vault") (part "RES-2"))
    )
    (comp (ref "R27")
      (value "330")
      (footprint "RESC3116X65X40LL10T20")
      (description "Chip Resistor, 330 Ohm, +/- 1%, 250 mW, -55 to 155 degC, 1206 (3216 Metric), RoHS, Tape and Reel")
      (fields (field (name "MANUFACTURER") "Yageo") (field (name "TOLERANCE") "1%"))
      (libsource (lib "Altium Content Vault") (part "RES-2"))
    )
    (comp (ref "R28")
      (value "10 k")
      (footprint "RESC3116X65X40ML10T20")
      (description "Chip Resistor, 10 KOhm, +/- 1%, 0.25 W, -55 to 155 degC, 1206 (3216 Metric), RoHS, Tape and Reel")
      (fields (field (name "TOLERANCE") "1%") (field (name "MANUFACTURER") "Yageo"))
      (libsource (lib "Altium Content Vault") (part "RES-2"))
    )
    (comp (ref "R29")
      (value "10 k")
      (footprint "RESC3116X65X40ML10T20")
      (description "Chip Resistor, 10 KOhm, +/- 1%, 0.25 W, -55 to 155 degC, 1206 (3216 Metric), RoHS, Tape and Reel")
      (fields (field (name "TOLERANCE") "1%") (field (name "MANUFACTURER") "Yageo"))
      (libsource (lib "Altium Content Vault") (part "RES-2"))
    )
    (comp (ref "R30")
      (value "4.7 k")
      (footprint "YAGO-RC0805_M")
      (fields
        (field (name "TOLERANCE") "+/- 1%")
        (field (name "PARTNUMBER") "RC0805FR-074K7L")
        (field (name "POWER") "0.125 W")
      )
      (libsource (lib "Altium Content Vault") (part "YAGO-RES-2"))
    )
    (comp (ref "R31")
      (value "4.7 k")
      (footprint "YAGO-RC0805_M")
      (fields
        (field (name "TOLERANCE") "+/- 1%")
        (field (name "PARTNUMBER") "RC0805FR-074K7L")
        (field (name "POWER") "0.125 W")
      )
      (libsource (lib "Altium Content Vault") (part "YAGO-RES-2"))
    )
    (comp (ref "R32")
      (value "330")
      (footprint "RESC3116X65X40LL10T20")
      (description "Chip Resistor, 330 Ohm, +/- 1%, 250 mW, -55 to 155 degC, 1206 (3216 Metric), RoHS, Tape and Reel")
      (fields (field (name "MANUFACTURER") "Yageo") (field (name "TOLERANCE") "1%"))
      (libsource (lib "Altium Content Vault") (part "RES-2"))
    )
    (comp (ref "R33")
      (value "330")
      (footprint "RESC3116X65X40LL10T20")
      (description "Chip Resistor, 330 Ohm, +/- 1%, 250 mW, -55 to 155 degC, 1206 (3216 Metric), RoHS, Tape and Reel")
      (fields (field (name "MANUFACTURER") "Yageo") (field (name "TOLERANCE") "1%"))
      (libsource (lib "Altium Content Vault") (part "RES-2"))
    )
    (comp (ref "R34")
      (value "330")
      (footprint "RESC3116X65X40LL10T20")
      (description "Chip Resistor, 330 Ohm, +/- 1%, 250 mW, -55 to 155 degC, 1206 (3216 Metric), RoHS, Tape and Reel")
      (fields (field (name "MANUFACTURER") "Yageo") (field (name "TOLERANCE") "1%"))
      (libsource (lib "Altium Content Vault") (part "RES-2"))
    )
    (comp (ref "R35")
      (value "330")
      (footprint "RESC3116X65X40LL10T20")
      (description "Chip Resistor, 330 Ohm, +/- 1%, 250 mW, -55 to 155 degC, 1206 (3216 Metric), RoHS, Tape and Reel")
      (fields (field (name "MANUFACTURER") "Yageo") (field (name "TOLERANCE") "1%"))
      (libsource (lib "Altium Content Vault") (part "RES-2"))
    )
    (comp (ref "U1")
      (value "NE555DR")
      (footprint "D0008A_L")
      (libsource (lib "Altium Content Vault") (part "CMP-1685-00007-1"))
    )
    (comp (ref "U2")
      (value "NE555DR")
      (footprint "D0008A_L")
      (libsource (lib "Altium Content Vault") (part "CMP-1685-00007-1"))
    )
    (comp (ref "U3")
      (value "NE555DR")
      (footprint "D0008A_L")
      (libsource (lib "Altium Content Vault") (part "CMP-1685-00007-1"))
    )
    (comp (ref "U4")
      (value "NE555DR")
      (footprint "D0008A_L")
      (libsource (lib "Altium Content Vault") (part "CMP-1685-00007-1"))
    )
    (comp (ref "U5")
      (value "NE555DR")
      (footprint "D0008A_L")
      (libsource (lib "Altium Content Vault") (part "CMP-1685-00007-1"))
    )
  )
  (nets
    (net (code "1") (name "/+ Valve 1") (class "Default")
      (node (ref "D2") (pin "2") (pinfunction "K_2") (pintype "passive"))
      (node (ref "D3") (pin "2") (pinfunction "K_2") (pintype "passive"))
      (node (ref "P1") (pin "1") (pinfunction "1_1") (pintype "passive"))
      (node (ref "Q2") (pin "4") (pinfunction "C_4") (pintype "passive"))
    )
    (net (code "2") (name "/+ Valve 2") (class "Default")
      (node (ref "D7") (pin "2") (pinfunction "K_2") (pintype "passive"))
      (node (ref "D89") (pin "2") (pinfunction "K_2") (pintype "passive"))
      (node (ref "P2") (pin "1") (pinfunction "1_1") (pintype "passive"))
      (node (ref "Q7") (pin "4") (pinfunction "C_4") (pintype "passive"))
    )
    (net (code "3") (name "/+ Valve 3") (class "Default")
      (node (ref "D11") (pin "2") (pinfunction "K_2") (pintype "passive"))
      (node (ref "D9") (pin "2") (pinfunction "K_2") (pintype "passive"))
      (node (ref "P3") (pin "1") (pinfunction "1_1") (pintype "passive"))
      (node (ref "Q8") (pin "4") (pinfunction "C_4") (pintype "passive"))
    )
    (net (code "4") (name "/+ Valve 4") (class "Default")
      (node (ref "D15") (pin "1") (pinfunction "A_1") (pintype "passive"))
      (node (ref "D17") (pin "2") (pinfunction "K_2") (pintype "passive"))
      (node (ref "P5") (pin "1") (pinfunction "1_1") (pintype "passive"))
      (node (ref "Q15") (pin "4") (pinfunction "C_4") (pintype "passive"))
    )
    (net (code "5") (name "/+ Valve 5") (class "Default")
      (node (ref "D16") (pin "2") (pinfunction "K_2") (pintype "passive"))
      (node (ref "D18") (pin "2") (pinfunction "K_2") (pintype "passive"))
      (node (ref "P4") (pin "1") (pinfunction "1_1") (pintype "passive"))
      (node (ref "Q16") (pin "4") (pinfunction "C_4") (pintype "passive"))
    )
    (net (code "6") (name "/- Valve 1") (class "Default")
      (node (ref "D4") (pin "2") (pinfunction "K_2") (pintype "passive"))
      (node (ref "P1") (pin "2") (pinfunction "2_2") (pintype "passive"))
      (node (ref "Q4") (pin "4") (pinfunction "C_4") (pintype "passive"))
    )
    (net (code "7") (name "/- Valve 2") (class "Default")
      (node (ref "D10") (pin "2") (pinfunction "K_2") (pintype "passive"))
      (node (ref "P2") (pin "2") (pinfunction "2_2") (pintype "passive"))
      (node (ref "Q10") (pin "4") (pinfunction "C_4") (pintype "passive"))
    )
    (net (code "8") (name "/- Valve 3") (class "Default")
      (node (ref "D12") (pin "2") (pinfunction "K_2") (pintype "passive"))
      (node (ref "P3") (pin "2") (pinfunction "2_2") (pintype "passive"))
      (node (ref "Q12") (pin "4") (pinfunction "C_4") (pintype "passive"))
    )
    (net (code "9") (name "/- Valve 4") (class "Default")
      (node (ref "D19") (pin "2") (pinfunction "K_2") (pintype "passive"))
      (node (ref "P5") (pin "2") (pinfunction "2_2") (pintype "passive"))
      (node (ref "Q19") (pin "4") (pinfunction "C_4") (pintype "passive"))
    )
    (net (code "10") (name "/- Valve 5") (class "Default")
      (node (ref "D20") (pin "2") (pinfunction "K_2") (pintype "passive"))
      (node (ref "P4") (pin "2") (pinfunction "2_2") (pintype "passive"))
      (node (ref "Q20") (pin "4") (pinfunction "C_4") (pintype "passive"))
    )
    (net (code "11") (name "/Signal + 1") (class "Default")
      (node (ref "C1") (pin "1") (pinfunction "1_1") (pintype "passive"))
      (node (ref "PC-1") (pin "H1_1") (pinfunction "H1_1_H1_1") (pintype "passive"))
      (node (ref "R6") (pin "2") (pinfunction "2_2") (pintype "passive"))
    )
    (net (code "12") (name "/Signal + 2") (class "Default")
      (node (ref "C4") (pin "1") (pinfunction "1_1") (pintype "passive"))
      (node (ref "PC-1") (pin "H1_3") (pinfunction "H1_3_H1_3") (pintype "passive"))
      (node (ref "R16") (pin "2") (pinfunction "2_2") (pintype "passive"))
    )
    (net (code "13") (name "/Signal + 3") (class "Default")
      (node (ref "C7") (pin "1") (pinfunction "1_1") (pintype "passive"))
      (node (ref "PC-1") (pin "H1_5") (pinfunction "H1_5_H1_5") (pintype "passive"))
      (node (ref "R20") (pin "2") (pinfunction "2_2") (pintype "passive"))
    )
    (net (code "14") (name "/Signal + 4") (class "Default")
      (node (ref "C10") (pin "1") (pinfunction "1_1") (pintype "passive"))
      (node (ref "PC-1") (pin "H1_7") (pinfunction "H1_7_H1_7") (pintype "passive"))
      (node (ref "R32") (pin "2") (pinfunction "2_2") (pintype "passive"))
    )
    (net (code "15") (name "/Signal + 5") (class "Default")
      (node (ref "C11") (pin "1") (pinfunction "1_1") (pintype "passive"))
      (node (ref "PC-1") (pin "H1_9") (pinfunction "H1_9_H1_9") (pintype "passive"))
      (node (ref "R33") (pin "2") (pinfunction "2_2") (pintype "passive"))
    )
    (net (code "16") (name "/V1") (class "Default")
      (node (ref "2") (pin "1") (pinfunction "VOUT_1") (pintype "passive"))
      (node (ref "Q15") (pin "3") (pinfunction "E_3") (pintype "passive"))
      (node (ref "Q16") (pin "3") (pinfunction "E_3") (pintype "passive"))
      (node (ref "Q2") (pin "3") (pinfunction "E_3") (pintype "passive"))
      (node (ref "Q7") (pin "3") (pinfunction "E_3") (pintype "passive"))
      (node (ref "Q8") (pin "3") (pinfunction "E_3") (pintype "passive"))
      (node (ref "R14") (pin "1") (pinfunction "1_1") (pintype "passive"))
      (node (ref "R18") (pin "1") (pinfunction "1_1") (pintype "passive"))
      (node (ref "R28") (pin "1") (pinfunction "1_1") (pintype "passive"))
      (node (ref "R29") (pin "1") (pinfunction "1_1") (pintype "passive"))
      (node (ref "R4") (pin "1") (pinfunction "1_1") (pintype "passive"))
    )
    (net (code "17") (name "/V2") (class "Default")
      (node (ref "D15") (pin "2") (pinfunction "K_2") (pintype "passive"))
      (node (ref "D16") (pin "1") (pinfunction "A_1") (pintype "passive"))
      (node (ref "D2") (pin "1") (pinfunction "A_1") (pintype "passive"))
      (node (ref "D7") (pin "1") (pinfunction "A_1") (pintype "passive"))
      (node (ref "D9") (pin "1") (pinfunction "A_1") (pintype "passive"))
      (node (ref "PC-1") (pin "H2_27") (pinfunction "H2_27_H2_27") (pintype "passive"))
    )
    (net (code "18") (name "/Vcc") (class "Default")
      (node (ref "PC-1") (pin "H2_46") (pinfunction "H2_46_H2_46") (pintype "passive"))
      (node (ref "R1") (pin "1") (pinfunction "1_1") (pintype "passive"))
      (node (ref "R10") (pin "1") (pinfunction "1_1") (pintype "passive"))
      (node (ref "R11") (pin "2") (pinfunction "2_2") (pintype "passive"))
      (node (ref "R2") (pin "2") (pinfunction "2_2") (pintype "passive"))
      (node (ref "R22") (pin "1") (pinfunction "1_1") (pintype "passive"))
      (node (ref "R23") (pin "1") (pinfunction "1_1") (pintype "passive"))
      (node (ref "R24") (pin "2") (pinfunction "2_2") (pintype "passive"))
      (node (ref "R25") (pin "2") (pinfunction "2_2") (pintype "passive"))
      (node (ref "R8") (pin "1") (pinfunction "1_1") (pintype "passive"))
      (node (ref "R9") (pin "2") (pinfunction "2_2") (pintype "passive"))
      (node (ref "U1") (pin "4") (pinfunction "~{RESET}_4") (pintype "input"))
      (node (ref "U1") (pin "8") (pinfunction "VCC_8") (pintype "power_in"))
      (node (ref "U2") (pin "4") (pinfunction "~{RESET}_4") (pintype "input"))
      (node (ref "U2") (pin "8") (pinfunction "VCC_8") (pintype "power_in"))
      (node (ref "U3") (pin "4") (pinfunction "~{RESET}_4") (pintype "input"))
      (node (ref "U3") (pin "8") (pinfunction "VCC_8") (pintype "power_in"))
      (node (ref "U4") (pin "4") (pinfunction "~{RESET}_4") (pintype "input"))
      (node (ref "U4") (pin "8") (pinfunction "VCC_8") (pintype "power_in"))
      (node (ref "U5") (pin "4") (pinfunction "~{RESET}_4") (pintype "input"))
      (node (ref "U5") (pin "8") (pinfunction "VCC_8") (pintype "power_in"))
    )
    (net (code "19") (name "GND") (class "Default")
      (node (ref "C12") (pin "1") (pinfunction "1_1") (pintype "passive"))
      (node (ref "C13") (pin "1") (pinfunction "1_1") (pintype "passive"))
      (node (ref "C14") (pin "1") (pinfunction "1_1") (pintype "passive"))
      (node (ref "C15") (pin "1") (pinfunction "1_1") (pintype "passive"))
      (node (ref "C2") (pin "1") (pinfunction "1_1") (pintype "passive"))
      (node (ref "C3") (pin "1") (pinfunction "1_1") (pintype "passive"))
      (node (ref "C5") (pin "1") (pinfunction "1_1") (pintype "passive"))
      (node (ref "C6") (pin "1") (pinfunction "1_1") (pintype "passive"))
      (node (ref "C8") (pin "1") (pinfunction "1_1") (pintype "passive"))
      (node (ref "C9") (pin "1") (pinfunction "1_1") (pintype "passive"))
      (node (ref "D1") (pin "1") (pinfunction "A_1") (pintype "passive"))
      (node (ref "D13") (pin "1") (pinfunction "A_1") (pintype "passive"))
      (node (ref "D14") (pin "1") (pinfunction "A_1") (pintype "passive"))
      (node (ref "D5") (pin "1") (pinfunction "A_1") (pintype "passive"))
      (node (ref "D6") (pin "1") (pinfunction "A_1") (pintype "passive"))
      (node (ref "PC-1") (pin "H2_29") (pinfunction "H2_29_H2_29") (pintype "passive"))
      (node (ref "Q1") (pin "2") (pinfunction "E_2") (pintype "passive"))
      (node (ref "Q10") (pin "3") (pinfunction "E_3") (pintype "passive"))
      (node (ref "Q11") (pin "2") (pinfunction "E_2") (pintype "passive"))
      (node (ref "Q12") (pin "3") (pinfunction "E_3") (pintype "passive"))
      (node (ref "Q13") (pin "2") (pinfunction "E_2") (pintype "passive"))
      (node (ref "Q14") (pin "2") (pinfunction "E_2") (pintype "passive"))
      (node (ref "Q17") (pin "2") (pinfunction "E_2") (pintype "passive"))
      (node (ref "Q18") (pin "2") (pinfunction "E_2") (pintype "passive"))
      (node (ref "Q19") (pin "3") (pinfunction "E_3") (pintype "passive"))
      (node (ref "Q20") (pin "3") (pinfunction "E_3") (pintype "passive"))
      (node (ref "Q3") (pin "2") (pinfunction "E_2") (pintype "passive"))
      (node (ref "Q4") (pin "3") (pinfunction "E_3") (pintype "passive"))
      (node (ref "Q5") (pin "2") (pinfunction "E_2") (pintype "passive"))
      (node (ref "Q6") (pin "2") (pinfunction "E_2") (pintype "passive"))
      (node (ref "Q9") (pin "2") (pinfunction "E_2") (pintype "passive"))
      (node (ref "U1") (pin "1") (pinfunction "GND_1") (pintype "output"))
      (node (ref "U2") (pin "1") (pinfunction "GND_1") (pintype "output"))
      (node (ref "U3") (pin "1") (pinfunction "GND_1") (pintype "output"))
      (node (ref "U4") (pin "1") (pinfunction "GND_1") (pintype "output"))
      (node (ref "U5") (pin "1") (pinfunction "GND_1") (pintype "output"))
    )
    (net (code "20") (name "Net-(C1-Pad2)") (class "Default")
      (node (ref "C1") (pin "2") (pinfunction "2_2") (pintype "passive"))
      (node (ref "R3") (pin "1") (pinfunction "1_1") (pintype "passive"))
    )
    (net (code "21") (name "Net-(C4-Pad2)") (class "Default")
      (node (ref "C4") (pin "2") (pinfunction "2_2") (pintype "passive"))
      (node (ref "R12") (pin "1") (pinfunction "1_1") (pintype "passive"))
    )
    (net (code "22") (name "Net-(C7-Pad2)") (class "Default")
      (node (ref "C7") (pin "2") (pinfunction "2_2") (pintype "passive"))
      (node (ref "R13") (pin "1") (pinfunction "1_1") (pintype "passive"))
    )
    (net (code "23") (name "Net-(C10-Pad2)") (class "Default")
      (node (ref "C10") (pin "2") (pinfunction "2_2") (pintype "passive"))
      (node (ref "R26") (pin "1") (pinfunction "1_1") (pintype "passive"))
    )
    (net (code "24") (name "Net-(C11-Pad2)") (class "Default")
      (node (ref "C11") (pin "2") (pinfunction "2_2") (pintype "passive"))
      (node (ref "R27") (pin "1") (pinfunction "1_1") (pintype "passive"))
    )
    (net (code "25") (name "Net-(D1-K)") (class "Default")
      (node (ref "D1") (pin "2") (pinfunction "K_2") (pintype "passive"))
      (node (ref "Q1") (pin "1") (pinfunction "B_1") (pintype "passive"))
      (node (ref "R3") (pin "2") (pinfunction "2_2") (pintype "passive"))
    )
    (net (code "26") (name "Net-(D3-A)") (class "Default")
      (node (ref "D3") (pin "1") (pinfunction "A_1") (pintype "passive"))
      (node (ref "D4") (pin "1") (pinfunction "A_1") (pintype "passive"))
    )
    (net (code "27") (name "Net-(D5-K)") (class "Default")
      (node (ref "D5") (pin "2") (pinfunction "K_2") (pintype "passive"))
      (node (ref "Q5") (pin "1") (pinfunction "B_1") (pintype "passive"))
      (node (ref "R12") (pin "2") (pinfunction "2_2") (pintype "passive"))
    )
    (net (code "28") (name "Net-(D6-K)") (class "Default")
      (node (ref "D6") (pin "2") (pinfunction "K_2") (pintype "passive"))
      (node (ref "Q6") (pin "1") (pinfunction "B_1") (pintype "passive"))
      (node (ref "R13") (pin "2") (pinfunction "2_2") (pintype "passive"))
    )
    (net (code "29") (name "Net-(D10-A)") (class "Default")
      (node (ref "D10") (pin "1") (pinfunction "A_1") (pintype "passive"))
      (node (ref "D89") (pin "1") (pinfunction "A_1") (pintype "passive"))
    )
    (net (code "30") (name "Net-(D11-A)") (class "Default")
      (node (ref "D11") (pin "1") (pinfunction "A_1") (pintype "passive"))
      (node (ref "D12") (pin "1") (pinfunction "A_1") (pintype "passive"))
    )
    (net (code "31") (name "Net-(D13-K)") (class "Default")
      (node (ref "D13") (pin "2") (pinfunction "K_2") (pintype "passive"))
      (node (ref "Q13") (pin "1") (pinfunction "B_1") (pintype "passive"))
      (node (ref "R26") (pin "2") (pinfunction "2_2") (pintype "passive"))
    )
    (net (code "32") (name "Net-(D14-K)") (class "Default")
      (node (ref "D14") (pin "2") (pinfunction "K_2") (pintype "passive"))
      (node (ref "Q14") (pin "1") (pinfunction "B_1") (pintype "passive"))
      (node (ref "R27") (pin "2") (pinfunction "2_2") (pintype "passive"))
    )
    (net (code "33") (name "Net-(D17-A)") (class "Default")
      (node (ref "D17") (pin "1") (pinfunction "A_1") (pintype "passive"))
      (node (ref "D19") (pin "1") (pinfunction "A_1") (pintype "passive"))
    )
    (net (code "34") (name "Net-(D18-A)") (class "Default")
      (node (ref "D18") (pin "1") (pinfunction "A_1") (pintype "passive"))
      (node (ref "D20") (pin "1") (pinfunction "A_1") (pintype "passive"))
    )
    (net (code "35") (name "Net-(Q1-C)") (class "Default")
      (node (ref "Q1") (pin "3") (pinfunction "C_3") (pintype "passive"))
      (node (ref "R2") (pin "1") (pinfunction "1_1") (pintype "passive"))
      (node (ref "U1") (pin "2") (pinfunction "TRIG_2") (pintype "input"))
    )
    (net (code "36") (name "Net-(Q2-B)") (class "Default")
      (node (ref "Q2") (pin "1") (pinfunction "B_1") (pintype "passive"))
      (node (ref "R5") (pin "2") (pinfunction "2_2") (pintype "passive"))
    )
    (net (code "37") (name "Net-(Q3-B)") (class "Default")
      (node (ref "Q3") (pin "1") (pinfunction "B_1") (pintype "passive"))
      (node (ref "R7") (pin "1") (pinfunction "1_1") (pintype "passive"))
    )
    (net (code "38") (name "Net-(Q3-C)") (class "Default")
      (node (ref "Q3") (pin "3") (pinfunction "C_3") (pintype "passive"))
      (node (ref "R4") (pin "2") (pinfunction "2_2") (pintype "passive"))
      (node (ref "R5") (pin "1") (pinfunction "1_1") (pintype "passive"))
    )
    (net (code "39") (name "Net-(Q4-B)") (class "Default")
      (node (ref "Q4") (pin "1") (pinfunction "B_1") (pintype "passive"))
      (node (ref "R6") (pin "1") (pinfunction "1_1") (pintype "passive"))
    )
    (net (code "40") (name "Net-(Q5-C)") (class "Default")
      (node (ref "Q5") (pin "3") (pinfunction "C_3") (pintype "passive"))
      (node (ref "R9") (pin "1") (pinfunction "1_1") (pintype "passive"))
      (node (ref "U2") (pin "2") (pinfunction "TRIG_2") (pintype "input"))
    )
    (net (code "41") (name "Net-(Q6-C)") (class "Default")
      (node (ref "Q6") (pin "3") (pinfunction "C_3") (pintype "passive"))
      (node (ref "R11") (pin "1") (pinfunction "1_1") (pintype "passive"))
      (node (ref "U3") (pin "2") (pinfunction "TRIG_2") (pintype "input"))
    )
    (net (code "42") (name "Net-(Q7-B)") (class "Default")
      (node (ref "Q7") (pin "1") (pinfunction "B_1") (pintype "passive"))
      (node (ref "R15") (pin "2") (pinfunction "2_2") (pintype "passive"))
    )
    (net (code "43") (name "Net-(Q8-B)") (class "Default")
      (node (ref "Q8") (pin "1") (pinfunction "B_1") (pintype "passive"))
      (node (ref "R19") (pin "2") (pinfunction "2_2") (pintype "passive"))
    )
    (net (code "44") (name "Net-(Q9-B)") (class "Default")
      (node (ref "Q9") (pin "1") (pinfunction "B_1") (pintype "passive"))
      (node (ref "R17") (pin "1") (pinfunction "1_1") (pintype "passive"))
    )
    (net (code "45") (name "Net-(Q9-C)") (class "Default")
      (node (ref "Q9") (pin "3") (pinfunction "C_3") (pintype "passive"))
      (node (ref "R14") (pin "2") (pinfunction "2_2") (pintype "passive"))
      (node (ref "R15") (pin "1") (pinfunction "1_1") (pintype "passive"))
    )
    (net (code "46") (name "Net-(Q10-B)") (class "Default")
      (node (ref "Q10") (pin "1") (pinfunction "B_1") (pintype "passive"))
      (node (ref "R16") (pin "1") (pinfunction "1_1") (pintype "passive"))
    )
    (net (code "47") (name "Net-(Q11-B)") (class "Default")
      (node (ref "Q11") (pin "1") (pinfunction "B_1") (pintype "passive"))
      (node (ref "R21") (pin "1") (pinfunction "1_1") (pintype "passive"))
    )
    (net (code "48") (name "Net-(Q11-C)") (class "Default")
      (node (ref "Q11") (pin "3") (pinfunction "C_3") (pintype "passive"))
      (node (ref "R18") (pin "2") (pinfunction "2_2") (pintype "passive"))
      (node (ref "R19") (pin "1") (pinfunction "1_1") (pintype "passive"))
    )
    (net (code "49") (name "Net-(Q12-B)") (class "Default")
      (node (ref "Q12") (pin "1") (pinfunction "B_1") (pintype "passive"))
      (node (ref "R20") (pin "1") (pinfunction "1_1") (pintype "passive"))
    )
    (net (code "50") (name "Net-(Q13-C)") (class "Default")
      (node (ref "Q13") (pin "3") (pinfunction "C_3") (pintype "passive"))
      (node (ref "R24") (pin "1") (pinfunction "1_1") (pintype "passive"))
      (node (ref "U4") (pin "2") (pinfunction "TRIG_2") (pintype "input"))
    )
    (net (code "51") (name "Net-(Q14-C)") (class "Default")
      (node (ref "Q14") (pin "3") (pinfunction "C_3") (pintype "passive"))
      (node (ref "R25") (pin "1") (pinfunction "1_1") (pintype "passive"))
      (node (ref "U5") (pin "2") (pinfunction "TRIG_2") (pintype "input"))
    )
    (net (code "52") (name "Net-(Q15-B)") (class "Default")
      (node (ref "Q15") (pin "1") (pinfunction "B_1") (pintype "passive"))
      (node (ref "R30") (pin "2") (pinfunction "2_2") (pintype "passive"))
    )
    (net (code "53") (name "Net-(Q16-B)") (class "Default")
      (node (ref "Q16") (pin "1") (pinfunction "B_1") (pintype "passive"))
      (node (ref "R31") (pin "2") (pinfunction "2_2") (pintype "passive"))
    )
    (net (code "54") (name "Net-(Q17-B)") (class "Default")
      (node (ref "Q17") (pin "1") (pinfunction "B_1") (pintype "passive"))
      (node (ref "R34") (pin "1") (pinfunction "1_1") (pintype "passive"))
    )
    (net (code "55") (name "Net-(Q17-C)") (class "Default")
      (node (ref "Q17") (pin "3") (pinfunction "C_3") (pintype "passive"))
      (node (ref "R28") (pin "2") (pinfunction "2_2") (pintype "passive"))
      (node (ref "R30") (pin "1") (pinfunction "1_1") (pintype "passive"))
    )
    (net (code "56") (name "Net-(Q18-B)") (class "Default")
      (node (ref "Q18") (pin "1") (pinfunction "B_1") (pintype "passive"))
      (node (ref "R35") (pin "1") (pinfunction "1_1") (pintype "passive"))
    )
    (net (code "57") (name "Net-(Q18-C)") (class "Default")
      (node (ref "Q18") (pin "3") (pinfunction "C_3") (pintype "passive"))
      (node (ref "R29") (pin "2") (pinfunction "2_2") (pintype "passive"))
      (node (ref "R31") (pin "1") (pinfunction "1_1") (pintype "passive"))
    )
    (net (code "58") (name "Net-(Q19-B)") (class "Default")
      (node (ref "Q19") (pin "1") (pinfunction "B_1") (pintype "passive"))
      (node (ref "R32") (pin "1") (pinfunction "1_1") (pintype "passive"))
    )
    (net (code "59") (name "Net-(Q20-B)") (class "Default")
      (node (ref "Q20") (pin "1") (pinfunction "B_1") (pintype "passive"))
      (node (ref "R33") (pin "1") (pinfunction "1_1") (pintype "passive"))
    )
    (net (code "60") (name "Net-(U1-CONT)") (class "Default")
      (node (ref "C2") (pin "2") (pinfunction "2_2") (pintype "passive"))
      (node (ref "U1") (pin "5") (pinfunction "CONT_5") (pintype "bidirectional"))
    )
    (net (code "61") (name "Net-(U1-DISCH)") (class "Default")
      (node (ref "C3") (pin "2") (pinfunction "2_2") (pintype "passive"))
      (node (ref "R1") (pin "2") (pinfunction "2_2") (pintype "passive"))
      (node (ref "U1") (pin "6") (pinfunction "THRES_6") (pintype "input"))
      (node (ref "U1") (pin "7") (pinfunction "DISCH_7") (pintype "open_collector"))
    )
    (net (code "62") (name "Net-(U1-OUT)") (class "Default")
      (node (ref "R7") (pin "2") (pinfunction "2_2") (pintype "passive"))
      (node (ref "U1") (pin "3") (pinfunction "OUT_3") (pintype "output"))
    )
    (net (code "63") (name "Net-(U2-CONT)") (class "Default")
      (node (ref "C5") (pin "2") (pinfunction "2_2") (pintype "passive"))
      (node (ref "U2") (pin "5") (pinfunction "CONT_5") (pintype "bidirectional"))
    )
    (net (code "64") (name "Net-(U2-DISCH)") (class "Default")
      (node (ref "C6") (pin "2") (pinfunction "2_2") (pintype "passive"))
      (node (ref "R8") (pin "2") (pinfunction "2_2") (pintype "passive"))
      (node (ref "U2") (pin "6") (pinfunction "THRES_6") (pintype "input"))
      (node (ref "U2") (pin "7") (pinfunction "DISCH_7") (pintype "open_collector"))
    )
    (net (code "65") (name "Net-(U2-OUT)") (class "Default")
      (node (ref "R17") (pin "2") (pinfunction "2_2") (pintype "passive"))
      (node (ref "U2") (pin "3") (pinfunction "OUT_3") (pintype "output"))
    )
    (net (code "66") (name "Net-(U3-CONT)") (class "Default")
      (node (ref "C8") (pin "2") (pinfunction "2_2") (pintype "passive"))
      (node (ref "U3") (pin "5") (pinfunction "CONT_5") (pintype "bidirectional"))
    )
    (net (code "67") (name "Net-(U3-DISCH)") (class "Default")
      (node (ref "C9") (pin "2") (pinfunction "2_2") (pintype "passive"))
      (node (ref "R10") (pin "2") (pinfunction "2_2") (pintype "passive"))
      (node (ref "U3") (pin "6") (pinfunction "THRES_6") (pintype "input"))
      (node (ref "U3") (pin "7") (pinfunction "DISCH_7") (pintype "open_collector"))
    )
    (net (code "68") (name "Net-(U3-OUT)") (class "Default")
      (node (ref "R21") (pin "2") (pinfunction "2_2") (pintype "passive"))
      (node (ref "U3") (pin "3") (pinfunction "OUT_3") (pintype "output"))
    )
    (net (code "69") (name "Net-(U4-CONT)") (class "Default")
      (node (ref "C12") (pin "2") (pinfunction "2_2") (pintype "passive"))
      (node (ref "U4") (pin "5") (pinfunction "CONT_5") (pintype "bidirectional"))
    )
    (net (code "70") (name "Net-(U4-DISCH)") (class "Default")
      (node (ref "C14") (pin "2") (pinfunction "2_2") (pintype "passive"))
      (node (ref "R22") (pin "2") (pinfunction "2_2") (pintype "passive"))
      (node (ref "U4") (pin "6") (pinfunction "THRES_6") (pintype "input"))
      (node (ref "U4") (pin "7") (pinfunction "DISCH_7") (pintype "open_collector"))
    )
    (net (code "71") (name "Net-(U4-OUT)") (class "Default")
      (node (ref "R34") (pin "2") (pinfunction "2_2") (pintype "passive"))
      (node (ref "U4") (pin "3") (pinfunction "OUT_3") (pintype "output"))
    )
    (net (code "72") (name "Net-(U5-CONT)") (class "Default")
      (node (ref "C13") (pin "2") (pinfunction "2_2") (pintype "passive"))
      (node (ref "U5") (pin "5") (pinfunction "CONT_5") (pintype "bidirectional"))
    )
    (net (code "73") (name "Net-(U5-DISCH)") (class "Default")
      (node (ref "C15") (pin "2") (pinfunction "2_2") (pintype "passive"))
      (node (ref "R23") (pin "2") (pinfunction "2_2") (pintype "passive"))
      (node (ref "U5") (pin "6") (pinfunction "THRES_6") (pintype "input"))
      (node (ref "U5") (pin "7") (pinfunction "DISCH_7") (pintype "open_collector"))
    )
    (net (code "74") (name "Net-(U5-OUT)") (class "Default")
      (node (ref "R35") (pin "2") (pinfunction "2_2") (pintype "passive"))
      (node (ref "U5") (pin "3") (pinfunction "OUT_3") (pintype "output"))
    )
    (net (code "75") (name "unconnected-(2-GND-Pad2)") (class "Default")
      (node (ref "2") (pin "2") (pinfunction "GND_2") (pintype "passive"))
    )
    (net (code "76") (name "unconnected-(P1-PadMP1)") (class "Default")
      (node (ref "P1") (pin "MP1") (pinfunction "MP1_MP1") (pintype "passive"))
    )
    (net (code "77") (name "unconnected-(P1-PadMP2)") (class "Default")
      (node (ref "P1") (pin "MP2") (pinfunction "MP2_MP2") (pintype "passive"))
    )
    (net (code "78") (name "unconnected-(P2-PadMP1)") (class "Default")
      (node (ref "P2") (pin "MP1") (pinfunction "MP1_MP1") (pintype "passive"))
    )
    (net (code "79") (name "unconnected-(P2-PadMP2)") (class "Default")
      (node (ref "P2") (pin "MP2") (pinfunction "MP2_MP2") (pintype "passive"))
    )
    (net (code "80") (name "unconnected-(P3-PadMP1)") (class "Default")
      (node (ref "P3") (pin "MP1") (pinfunction "MP1_MP1") (pintype "passive"))
    )
    (net (code "81") (name "unconnected-(P3-PadMP2)") (class "Default")
      (node (ref "P3") (pin "MP2") (pinfunction "MP2_MP2") (pintype "passive"))
    )
    (net (code "82") (name "unconnected-(P4-PadMP1)") (class "Default")
      (node (ref "P4") (pin "MP1") (pinfunction "MP1_MP1") (pintype "passive"))
    )
    (net (code "83") (name "unconnected-(P4-PadMP2)") (class "Default")
      (node (ref "P4") (pin "MP2") (pinfunction "MP2_MP2") (pintype "passive"))
    )
    (net (code "84") (name "unconnected-(P5-PadMP1)") (class "Default")
      (node (ref "P5") (pin "MP1") (pinfunction "MP1_MP1") (pintype "passive"))
    )
    (net (code "85") (name "unconnected-(P5-PadMP2)") (class "Default")
      (node (ref "P5") (pin "MP2") (pinfunction "MP2_MP2") (pintype "passive"))
    )
    (net (code "86") (name "unconnected-(PC-1-PadH1_2)") (class "Default")
      (node (ref "PC-1") (pin "H1_2") (pinfunction "H1_2_H1_2") (pintype "passive"))
    )
    (net (code "87") (name "unconnected-(PC-1-PadH1_4)") (class "Default")
      (node (ref "PC-1") (pin "H1_4") (pinfunction "H1_4_H1_4") (pintype "passive"))
    )
    (net (code "88") (name "unconnected-(PC-1-PadH1_6)") (class "Default")
      (node (ref "PC-1") (pin "H1_6") (pinfunction "H1_6_H1_6") (pintype "passive"))
    )
    (net (code "89") (name "unconnected-(PC-1-PadH1_8)") (class "Default")
      (node (ref "PC-1") (pin "H1_8") (pinfunction "H1_8_H1_8") (pintype "passive"))
    )
    (net (code "90") (name "unconnected-(PC-1-PadH1_10)") (class "Default")
      (node (ref "PC-1") (pin "H1_10") (pinfunction "H1_10_H1_10") (pintype "passive"))
    )
    (net (code "91") (name "unconnected-(PC-1-PadH1_11)") (class "Default")
      (node (ref "PC-1") (pin "H1_11") (pinfunction "H1_11_H1_11") (pintype "passive"))
    )
    (net (code "92") (name "unconnected-(PC-1-PadH1_12)") (class "Default")
      (node (ref "PC-1") (pin "H1_12") (pinfunction "H1_12_H1_12") (pintype "passive"))
    )
    (net (code "93") (name "unconnected-(PC-1-PadH1_13)") (class "Default")
      (node (ref "PC-1") (pin "H1_13") (pinfunction "H1_13_H1_13") (pintype "passive"))
    )
    (net (code "94") (name "unconnected-(PC-1-PadH1_14)") (class "Default")
      (node (ref "PC-1") (pin "H1_14") (pinfunction "H1_14_H1_14") (pintype "passive"))
    )
    (net (code "95") (name "unconnected-(PC-1-PadH1_15)") (class "Default")
      (node (ref "PC-1") (pin "H1_15") (pinfunction "H1_15_H1_15") (pintype "passive"))
    )
    (net (code "96") (name "unconnected-(PC-1-PadH1_16)") (class "Default")
      (node (ref "PC-1") (pin "H1_16") (pinfunction "H1_16_H1_16") (pintype "passive"))
    )
    (net (code "97") (name "unconnected-(PC-1-PadH1_17)") (class "Default")
      (node (ref "PC-1") (pin "H1_17") (pinfunction "H1_17_H1_17") (pintype "passive"))
    )
    (net (code "98") (name "unconnected-(PC-1-PadH1_18)") (class "Default")
      (node (ref "PC-1") (pin "H1_18") (pinfunction "H1_18_H1_18") (pintype "passive"))
    )
    (net (code "99") (name "unconnected-(PC-1-PadH1_19)") (class "Default")
      (node (ref "PC-1") (pin "H1_19") (pinfunction "H1_19_H1_19") (pintype "passive"))
    )
    (net (code "100") (name "unconnected-(PC-1-PadH1_20)") (class "Default")
      (node (ref "PC-1") (pin "H1_20") (pinfunction "H1_20_H1_20") (pintype "passive"))
    )
    (net (code "101") (name "unconnected-(PC-1-PadH1_21)") (class "Default")
      (node (ref "PC-1") (pin "H1_21") (pinfunction "H1_21_H1_21") (pintype "passive"))
    )
    (net (code "102") (name "unconnected-(PC-1-PadH1_22)") (class "Default")
      (node (ref "PC-1") (pin "H1_22") (pinfunction "H1_22_H1_22") (pintype "passive"))
    )
    (net (code "103") (name "unconnected-(PC-1-PadH1_23)") (class "Default")
      (node (ref "PC-1") (pin "H1_23") (pinfunction "H1_23_H1_23") (pintype "passive"))
    )
    (net (code "104") (name "unconnected-(PC-1-PadH1_24)") (class "Default")
      (node (ref "PC-1") (pin "H1_24") (pinfunction "H1_24_H1_24") (pintype "passive"))
    )
    (net (code "105") (name "unconnected-(PC-1-PadH1_25)") (class "Default")
      (node (ref "PC-1") (pin "H1_25") (pinfunction "H1_25_H1_25") (pintype "passive"))
    )
    (net (code "106") (name "unconnected-(PC-1-PadH1_26)") (class "Default")
      (node (ref "PC-1") (pin "H1_26") (pinfunction "H1_26_H1_26") (pintype "passive"))
    )
    (net (code "107") (name "unconnected-(PC-1-PadH1_27)") (class "Default")
      (node (ref "PC-1") (pin "H1_27") (pinfunction "H1_27_H1_27") (pintype "passive"))
    )
    (net (code "108") (name "unconnected-(PC-1-PadH1_28)") (class "Default")
      (node (ref "PC-1") (pin "H1_28") (pinfunction "H1_28_H1_28") (pintype "passive"))
    )
    (net (code "109") (name "unconnected-(PC-1-PadH1_29)") (class "Default")
      (node (ref "PC-1") (pin "H1_29") (pinfunction "H1_29_H1_29") (pintype "passive"))
    )
    (net (code "110") (name "unconnected-(PC-1-PadH1_30)") (class "Default")
      (node (ref "PC-1") (pin "H1_30") (pinfunction "H1_30_H1_30") (pintype "passive"))
    )
    (net (code "111") (name "unconnected-(PC-1-PadH1_31)") (class "Default")
      (node (ref "PC-1") (pin "H1_31") (pinfunction "H1_31_H1_31") (pintype "passive"))
    )
    (net (code "112") (name "unconnected-(PC-1-PadH1_32)") (class "Default")
      (node (ref "PC-1") (pin "H1_32") (pinfunction "H1_32_H1_32") (pintype "passive"))
    )
    (net (code "113") (name "unconnected-(PC-1-PadH1_33)") (class "Default")
      (node (ref "PC-1") (pin "H1_33") (pinfunction "H1_33_H1_33") (pintype "passive"))
    )
    (net (code "114") (name "unconnected-(PC-1-PadH1_34)") (class "Default")
      (node (ref "PC-1") (pin "H1_34") (pinfunction "H1_34_H1_34") (pintype "passive"))
    )
    (net (code "115") (name "unconnected-(PC-1-PadH1_35)") (class "Default")
      (node (ref "PC-1") (pin "H1_35") (pinfunction "H1_35_H1_35") (pintype "passive"))
    )
    (net (code "116") (name "unconnected-(PC-1-PadH1_36)") (class "Default")
      (node (ref "PC-1") (pin "H1_36") (pinfunction "H1_36_H1_36") (pintype "passive"))
    )
    (net (code "117") (name "unconnected-(PC-1-PadH1_37)") (class "Default")
      (node (ref "PC-1") (pin "H1_37") (pinfunction "H1_37_H1_37") (pintype "passive"))
    )
    (net (code "118") (name "unconnected-(PC-1-PadH1_38)") (class "Default")
      (node (ref "PC-1") (pin "H1_38") (pinfunction "H1_38_H1_38") (pintype "passive"))
    )
    (net (code "119") (name "unconnected-(PC-1-PadH1_39)") (class "Default")
      (node (ref "PC-1") (pin "H1_39") (pinfunction "H1_39_H1_39") (pintype "passive"))
    )
    (net (code "120") (name "unconnected-(PC-1-PadH1_40)") (class "Default")
      (node (ref "PC-1") (pin "H1_40") (pinfunction "H1_40_H1_40") (pintype "passive"))
    )
    (net (code "121") (name "unconnected-(PC-1-PadH1_41)") (class "Default")
      (node (ref "PC-1") (pin "H1_41") (pinfunction "H1_41_H1_41") (pintype "passive"))
    )
    (net (code "122") (name "unconnected-(PC-1-PadH1_42)") (class "Default")
      (node (ref "PC-1") (pin "H1_42") (pinfunction "H1_42_H1_42") (pintype "passive"))
    )
    (net (code "123") (name "unconnected-(PC-1-PadH1_43)") (class "Default")
      (node (ref "PC-1") (pin "H1_43") (pinfunction "H1_43_H1_43") (pintype "passive"))
    )
    (net (code "124") (name "unconnected-(PC-1-PadH1_44)") (class "Default")
      (node (ref "PC-1") (pin "H1_44") (pinfunction "H1_44_H1_44") (pintype "passive"))
    )
    (net (code "125") (name "unconnected-(PC-1-PadH1_45)") (class "Default")
      (node (ref "PC-1") (pin "H1_45") (pinfunction "H1_45_H1_45") (pintype "passive"))
    )
    (net (code "126") (name "unconnected-(PC-1-PadH1_46)") (class "Default")
      (node (ref "PC-1") (pin "H1_46") (pinfunction "H1_46_H1_46") (pintype "passive"))
    )
    (net (code "127") (name "unconnected-(PC-1-PadH1_47)") (class "Default")
      (node (ref "PC-1") (pin "H1_47") (pinfunction "H1_47_H1_47") (pintype "passive"))
    )
    (net (code "128") (name "unconnected-(PC-1-PadH1_48)") (class "Default")
      (node (ref "PC-1") (pin "H1_48") (pinfunction "H1_48_H1_48") (pintype "passive"))
    )
    (net (code "129") (name "unconnected-(PC-1-PadH1_49)") (class "Default")
      (node (ref "PC-1") (pin "H1_49") (pinfunction "H1_49_H1_49") (pintype "passive"))
    )
    (net (code "130") (name "unconnected-(PC-1-PadH1_50)") (class "Default")
      (node (ref "PC-1") (pin "H1_50") (pinfunction "H1_50_H1_50") (pintype "passive"))
    )
    (net (code "131") (name "unconnected-(PC-1-PadH1_51)") (class "Default")
      (node (ref "PC-1") (pin "H1_51") (pinfunction "H1_51_H1_51") (pintype "passive"))
    )
    (net (code "132") (name "unconnected-(PC-1-PadH1_52)") (class "Default")
      (node (ref "PC-1") (pin "H1_52") (pinfunction "H1_52_H1_52") (pintype "passive"))
    )
    (net (code "133") (name "unconnected-(PC-1-PadH2_1)") (class "Default")
      (node (ref "PC-1") (pin "H2_1") (pinfunction "H2_1_H2_1") (pintype "passive"))
    )
    (net (code "134") (name "unconnected-(PC-1-PadH2_2)") (class "Default")
      (node (ref "PC-1") (pin "H2_2") (pinfunction "H2_2_H2_2") (pintype "passive"))
    )
    (net (code "135") (name "unconnected-(PC-1-PadH2_3)") (class "Default")
      (node (ref "PC-1") (pin "H2_3") (pinfunction "H2_3_H2_3") (pintype "passive"))
    )
    (net (code "136") (name "unconnected-(PC-1-PadH2_4)") (class "Default")
      (node (ref "PC-1") (pin "H2_4") (pinfunction "H2_4_H2_4") (pintype "passive"))
    )
    (net (code "137") (name "unconnected-(PC-1-PadH2_5)") (class "Default")
      (node (ref "PC-1") (pin "H2_5") (pinfunction "H2_5_H2_5") (pintype "passive"))
    )
    (net (code "138") (name "unconnected-(PC-1-PadH2_6)") (class "Default")
      (node (ref "PC-1") (pin "H2_6") (pinfunction "H2_6_H2_6") (pintype "passive"))
    )
    (net (code "139") (name "unconnected-(PC-1-PadH2_7)") (class "Default")
      (node (ref "PC-1") (pin "H2_7") (pinfunction "H2_7_H2_7") (pintype "passive"))
    )
    (net (code "140") (name "unconnected-(PC-1-PadH2_8)") (class "Default")
      (node (ref "PC-1") (pin "H2_8") (pinfunction "H2_8_H2_8") (pintype "passive"))
    )
    (net (code "141") (name "unconnected-(PC-1-PadH2_9)") (class "Default")
      (node (ref "PC-1") (pin "H2_9") (pinfunction "H2_9_H2_9") (pintype "passive"))
    )
    (net (code "142") (name "unconnected-(PC-1-PadH2_10)") (class "Default")
      (node (ref "PC-1") (pin "H2_10") (pinfunction "H2_10_H2_10") (pintype "passive"))
    )
    (net (code "143") (name "unconnected-(PC-1-PadH2_11)") (class "Default")
      (node (ref "PC-1") (pin "H2_11") (pinfunction "H2_11_H2_11") (pintype "passive"))
    )
    (net (code "144") (name "unconnected-(PC-1-PadH2_12)") (class "Default")
      (node (ref "PC-1") (pin "H2_12") (pinfunction "H2_12_H2_12") (pintype "passive"))
    )
    (net (code "145") (name "unconnected-(PC-1-PadH2_13)") (class "Default")
      (node (ref "PC-1") (pin "H2_13") (pinfunction "H2_13_H2_13") (pintype "passive"))
    )
    (net (code "146") (name "unconnected-(PC-1-PadH2_14)") (class "Default")
      (node (ref "PC-1") (pin "H2_14") (pinfunction "H2_14_H2_14") (pintype "passive"))
    )
    (net (code "147") (name "unconnected-(PC-1-PadH2_15)") (class "Default")
      (node (ref "PC-1") (pin "H2_15") (pinfunction "H2_15_H2_15") (pintype "passive"))
    )
    (net (code "148") (name "unconnected-(PC-1-PadH2_16)") (class "Default")
      (node (ref "PC-1") (pin "H2_16") (pinfunction "H2_16_H2_16") (pintype "passive"))
    )
    (net (code "149") (name "unconnected-(PC-1-PadH2_17)") (class "Default")
      (node (ref "PC-1") (pin "H2_17") (pinfunction "H2_17_H2_17") (pintype "passive"))
    )
    (net (code "150") (name "unconnected-(PC-1-PadH2_18)") (class "Default")
      (node (ref "PC-1") (pin "H2_18") (pinfunction "H2_18_H2_18") (pintype "passive"))
    )
    (net (code "151") (name "unconnected-(PC-1-PadH2_19)") (class "Default")
      (node (ref "PC-1") (pin "H2_19") (pinfunction "H2_19_H2_19") (pintype "passive"))
    )
    (net (code "152") (name "unconnected-(PC-1-PadH2_20)") (class "Default")
      (node (ref "PC-1") (pin "H2_20") (pinfunction "H2_20_H2_20") (pintype "passive"))
    )
    (net (code "153") (name "unconnected-(PC-1-PadH2_21)") (class "Default")
      (node (ref "PC-1") (pin "H2_21") (pinfunction "H2_21_H2_21") (pintype "passive"))
    )
    (net (code "154") (name "unconnected-(PC-1-PadH2_22)") (class "Default")
      (node (ref "PC-1") (pin "H2_22") (pinfunction "H2_22_H2_22") (pintype "passive"))
    )
    (net (code "155") (name "unconnected-(PC-1-PadH2_23)") (class "Default")
      (node (ref "PC-1") (pin "H2_23") (pinfunction "H2_23_H2_23") (pintype "passive"))
    )
    (net (code "156") (name "unconnected-(PC-1-PadH2_24)") (class "Default")
      (node (ref "PC-1") (pin "H2_24") (pinfunction "H2_24_H2_24") (pintype "passive"))
    )
    (net (code "157") (name "unconnected-(PC-1-PadH2_25)") (class "Default")
      (node (ref "PC-1") (pin "H2_25") (pinfunction "H2_25_H2_25") (pintype "passive"))
    )
    (net (code "158") (name "unconnected-(PC-1-PadH2_26)") (class "Default")
      (node (ref "PC-1") (pin "H2_26") (pinfunction "H2_26_H2_26") (pintype "passive"))
    )
    (net (code "159") (name "unconnected-(PC-1-PadH2_28)") (class "Default")
      (node (ref "PC-1") (pin "H2_28") (pinfunction "H2_28_H2_28") (pintype "passive"))
    )
    (net (code "160") (name "unconnected-(PC-1-PadH2_30)") (class "Default")
      (node (ref "PC-1") (pin "H2_30") (pinfunction "H2_30_H2_30") (pintype "passive"))
    )
    (net (code "161") (name "unconnected-(PC-1-PadH2_31)") (class "Default")
      (node (ref "PC-1") (pin "H2_31") (pinfunction "H2_31_H2_31") (pintype "passive"))
    )
    (net (code "162") (name "unconnected-(PC-1-PadH2_32)") (class "Default")
      (node (ref "PC-1") (pin "H2_32") (pinfunction "H2_32_H2_32") (pintype "passive"))
    )
    (net (code "163") (name "unconnected-(PC-1-PadH2_33)") (class "Default")
      (node (ref "PC-1") (pin "H2_33") (pinfunction "H2_33_H2_33") (pintype "passive"))
    )
    (net (code "164") (name "unconnected-(PC-1-PadH2_34)") (class "Default")
      (node (ref "PC-1") (pin "H2_34") (pinfunction "H2_34_H2_34") (pintype "passive"))
    )
    (net (code "165") (name "unconnected-(PC-1-PadH2_35)") (class "Default")
      (node (ref "PC-1") (pin "H2_35") (pinfunction "H2_35_H2_35") (pintype "passive"))
    )
    (net (code "166") (name "unconnected-(PC-1-PadH2_36)") (class "Default")
      (node (ref "PC-1") (pin "H2_36") (pinfunction "H2_36_H2_36") (pintype "passive"))
    )
    (net (code "167") (name "unconnected-(PC-1-PadH2_37)") (class "Default")
      (node (ref "PC-1") (pin "H2_37") (pinfunction "H2_37_H2_37") (pintype "passive"))
    )
    (net (code "168") (name "unconnected-(PC-1-PadH2_38)") (class "Default")
      (node (ref "PC-1") (pin "H2_38") (pinfunction "H2_38_H2_38") (pintype "passive"))
    )
    (net (code "169") (name "unconnected-(PC-1-PadH2_39)") (class "Default")
      (node (ref "PC-1") (pin "H2_39") (pinfunction "H2_39_H2_39") (pintype "passive"))
    )
    (net (code "170") (name "unconnected-(PC-1-PadH2_40)") (class "Default")
      (node (ref "PC-1") (pin "H2_40") (pinfunction "H2_40_H2_40") (pintype "passive"))
    )
    (net (code "171") (name "unconnected-(PC-1-PadH2_41)") (class "Default")
      (node (ref "PC-1") (pin "H2_41") (pinfunction "H2_41_H2_41") (pintype "passive"))
    )
    (net (code "172") (name "unconnected-(PC-1-PadH2_42)") (class "Default")
      (node (ref "PC-1") (pin "H2_42") (pinfunction "H2_42_H2_42") (pintype "passive"))
    )
    (net (code "173") (name "unconnected-(PC-1-PadH2_43)") (class "Default")
      (node (ref "PC-1") (pin "H2_43") (pinfunction "H2_43_H2_43") (pintype "passive"))
    )
    (net (code "174") (name "unconnected-(PC-1-PadH2_44)") (class "Default")
      (node (ref "PC-1") (pin "H2_44") (pinfunction "H2_44_H2_44") (pintype "passive"))
    )
    (net (code "175") (name "unconnected-(PC-1-PadH2_45)") (class "Default")
      (node (ref "PC-1") (pin "H2_45") (pinfunction "H2_45_H2_45") (pintype "passive"))
    )
    (net (code "176") (name "unconnected-(PC-1-PadH2_47)") (class "Default")
      (node (ref "PC-1") (pin "H2_47") (pinfunction "H2_47_H2_47") (pintype "passive"))
    )
    (net (code "177") (name "unconnected-(PC-1-PadH2_48)") (class "Default")
      (node (ref "PC-1") (pin "H2_48") (pinfunction "H2_48_H2_48") (pintype "passive"))
    )
    (net (code "178") (name "unconnected-(PC-1-PadH2_49)") (class "Default")
      (node (ref "PC-1") (pin "H2_49") (pinfunction "H2_49_H2_49") (pintype "passive"))
    )
    (net (code "179") (name "unconnected-(PC-1-PadH2_50)") (class "Default")
      (node (ref "PC-1") (pin "H2_50") (pinfunction "H2_50_H2_50") (pintype "passive"))
    )
    (net (code "180") (name "unconnected-(PC-1-PadH2_51)") (class "Default")
      (node (ref "PC-1") (pin "H2_51") (pinfunction "H2_51_H2_51") (pintype "passive"))
    )
    (net (code "181") (name "unconnected-(PC-1-PadH2_52)") (class "Default")
      (node (ref "PC-1") (pin "H2_52") (pinfunction "H2_52_H2_52") (pintype "passive"))
    )
  )
)
